# GBADVI.net
KiCad netlist of a schematic drawn in EAGLE
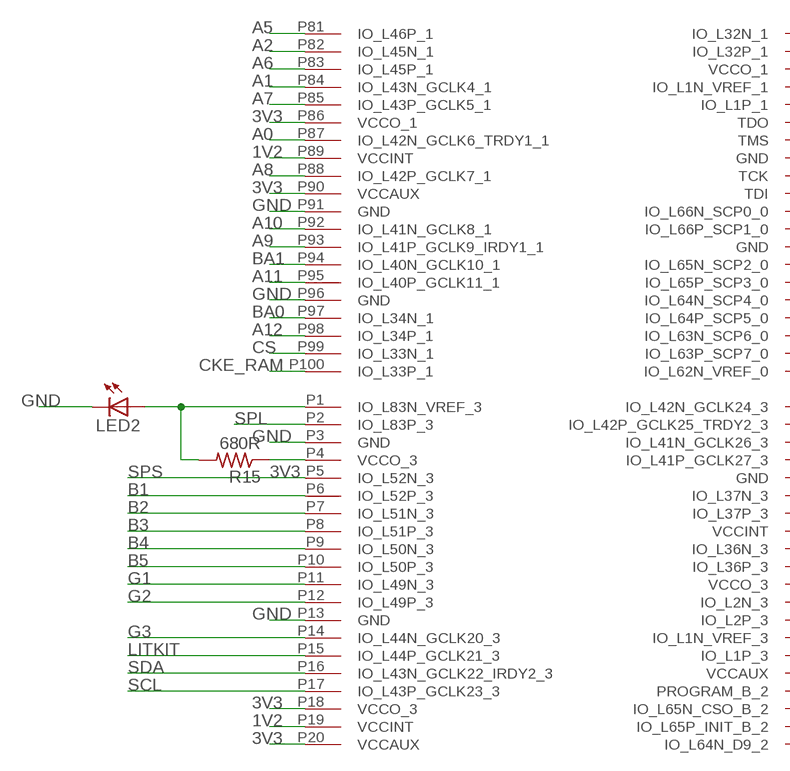
[diagram p0: schematic, sheet 1, part 1 of 2]
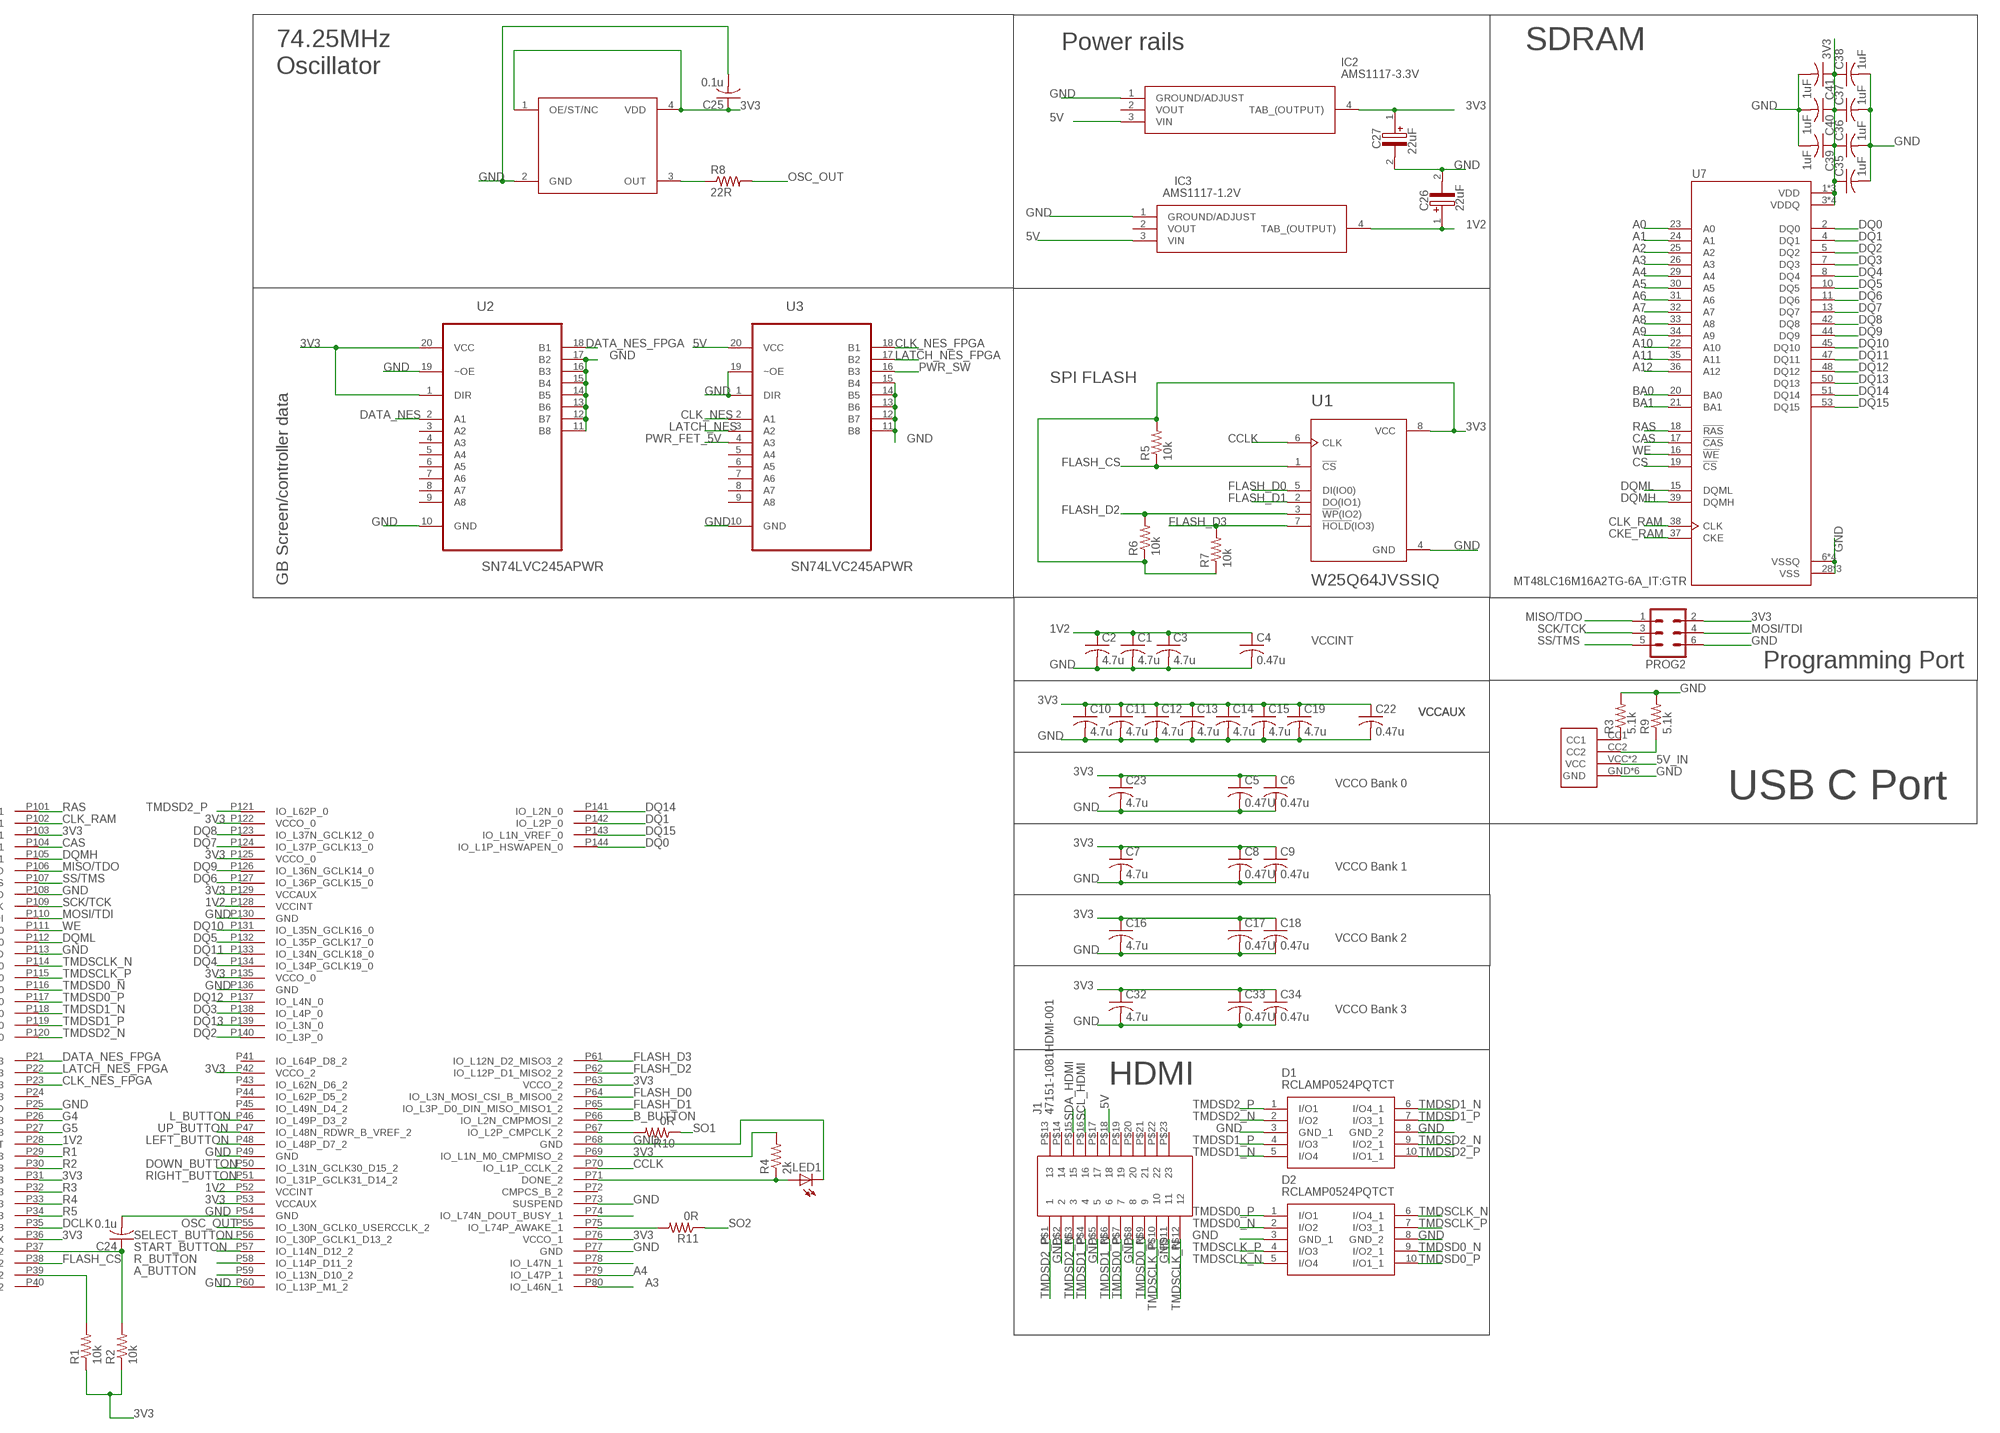
[diagram p1: schematic, sheet 1, part 2 of 2]
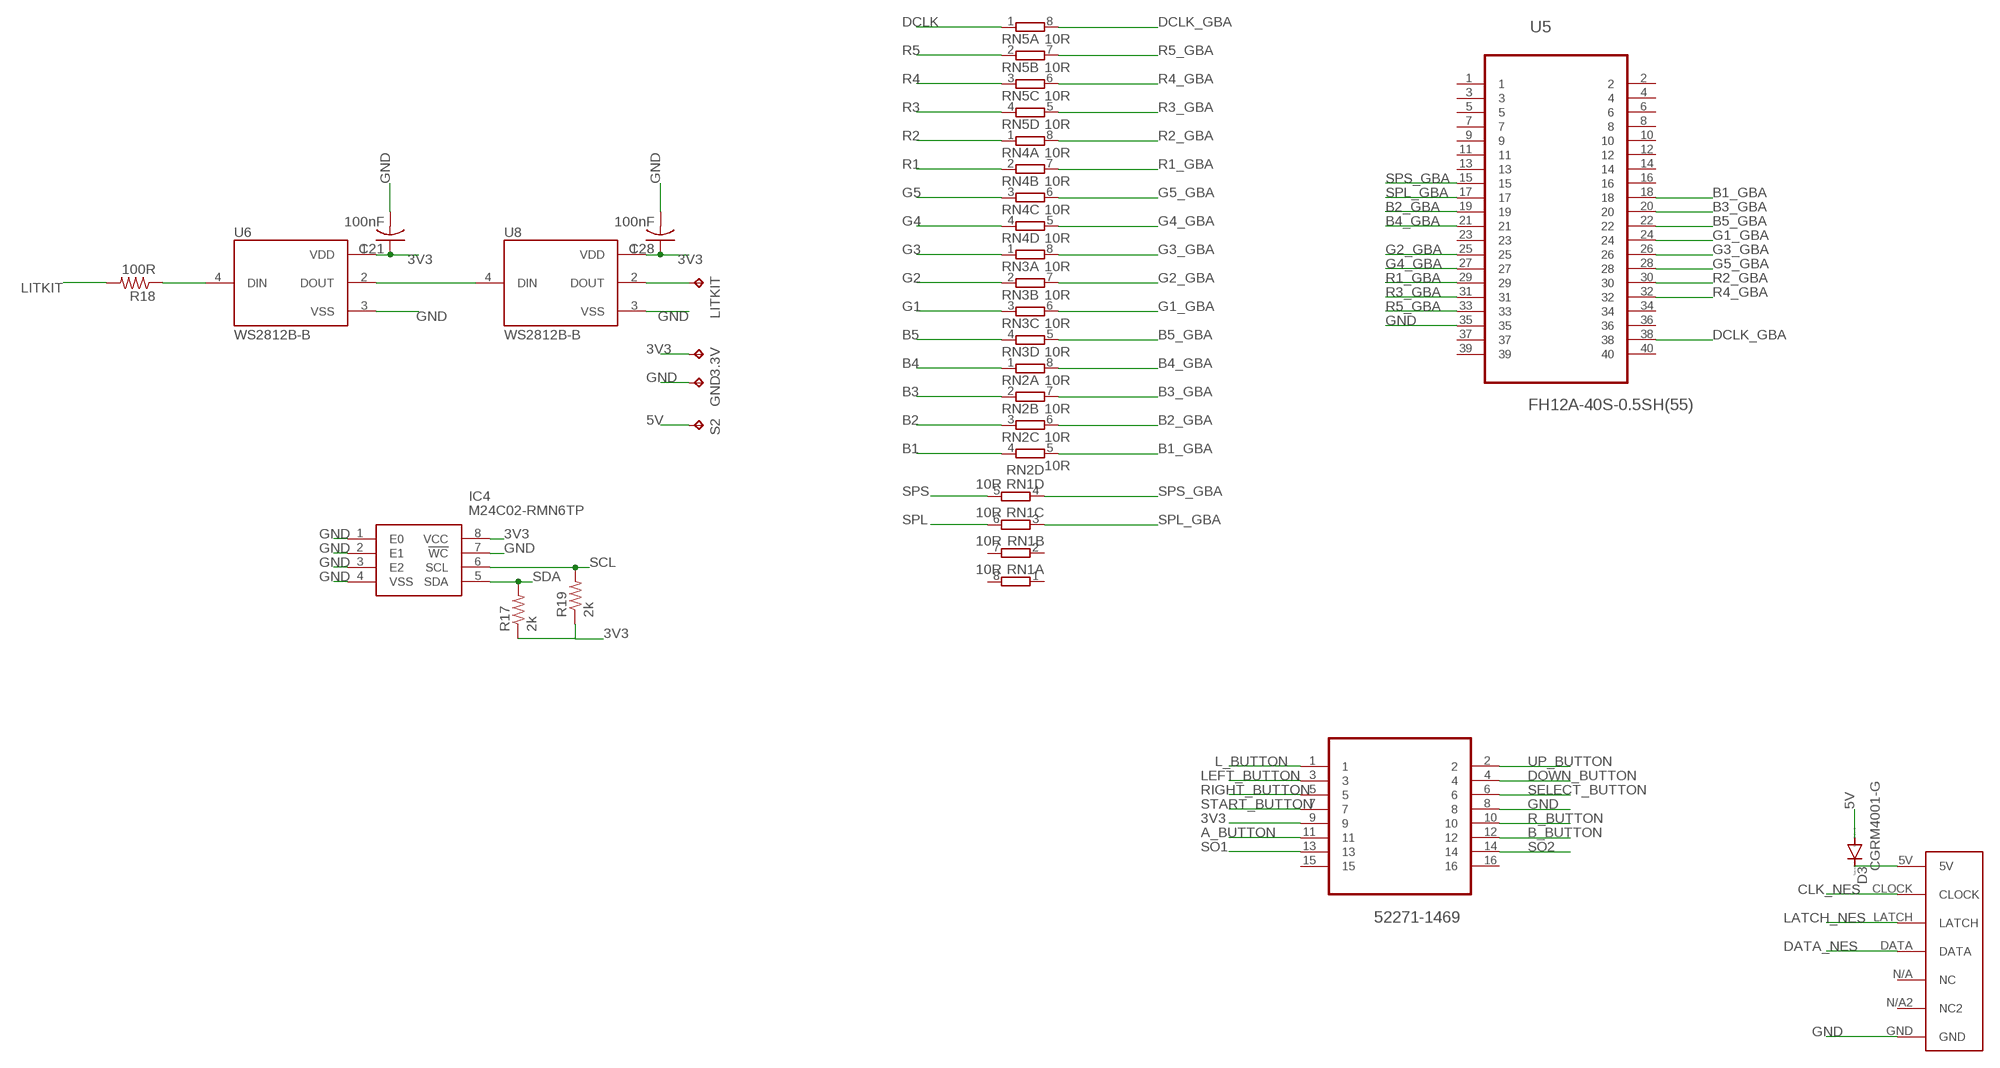
[diagram p2: schematic, sheet 2]
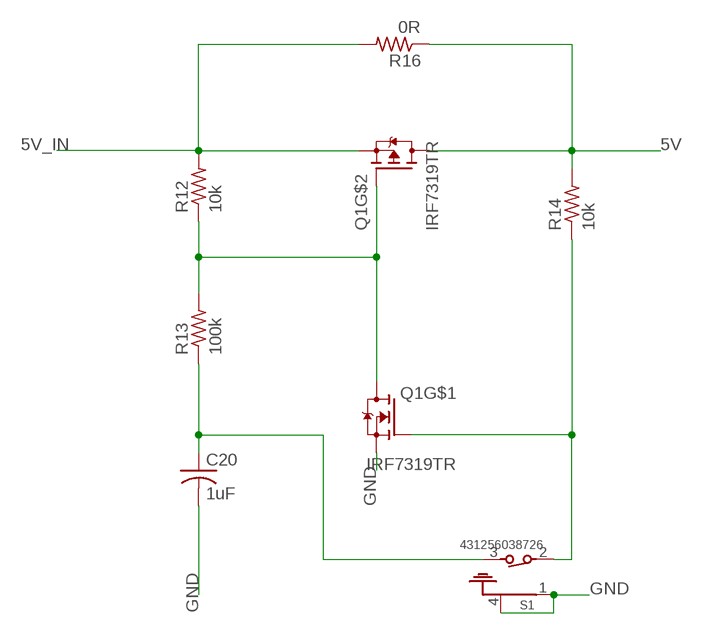
[diagram p3: schematic, sheet 3]

(export (version "E")
  (design (tool "Eeschema 10.0.6"))
  (components
    (comp (ref "3.3V")
      (value "TPB1,27")
      (footprint "eagle-import:B1,27")
      (libsource (lib "eagle-import") (part "TPB1,27"))
    )
    (comp (ref "C21")
      (value "100nF")
      (footprint "eagle-import:C0603")
      (libsource (lib "eagle-import") (part "C-USC0603"))
    )
    (comp (ref "C28")
      (value "100nF")
      (footprint "eagle-import:C0603")
      (libsource (lib "eagle-import") (part "C-USC0603"))
    )
    (comp (ref "D3")
      (value "CGRM4001-G")
      (footprint "eagle-import:SOD-123_MINI-SMA")
      (libsource (lib "eagle-import") (part "CGRM400-G1"))
    )
    (comp (ref "GND")
      (value "TPB1,27")
      (footprint "eagle-import:B1,27")
      (libsource (lib "eagle-import") (part "TPB1,27"))
    )
    (comp (ref "IC4")
      (value "M24C02-RMN6TP")
      (footprint "eagle-import:SOIC127P600X175-8N")
      (fields (field (name "MOUSER_PART_NUMBER") "511-M24C02-RMN6TP"))
      (libsource (lib "eagle-import") (part "M24C02-RMN6TP"))
    )
    (comp (ref "LITKIT")
      (value "TPB1,27")
      (footprint "eagle-import:B1,27")
      (libsource (lib "eagle-import") (part "TPB1,27"))
    )
    (comp (ref "R17")
      (value "2k")
      (footprint "eagle-import:R0603")
      (libsource (lib "eagle-import") (part "R-US_R0603"))
    )
    (comp (ref "R18")
      (value "100R")
      (footprint "eagle-import:R0603")
      (libsource (lib "eagle-import") (part "R-US_R0603"))
    )
    (comp (ref "R19")
      (value "2k")
      (footprint "eagle-import:R0603")
      (libsource (lib "eagle-import") (part "R-US_R0603"))
    )
    (comp (ref "RN1")
      (value "10R")
      (footprint "eagle-import:0603-ARV")
      (libsource (lib "eagle-import") (part "4R-N0603-ARV"))
    )
    (comp (ref "RN2")
      (value "10R")
      (footprint "eagle-import:0603-ARV")
      (libsource (lib "eagle-import") (part "4R-N0603-ARV"))
    )
    (comp (ref "RN3")
      (value "10R")
      (footprint "eagle-import:0603-ARV")
      (libsource (lib "eagle-import") (part "4R-N0603-ARV"))
    )
    (comp (ref "RN4")
      (value "10R")
      (footprint "eagle-import:0603-ARV")
      (libsource (lib "eagle-import") (part "4R-N0603-ARV"))
    )
    (comp (ref "RN5")
      (value "10R")
      (footprint "eagle-import:0603-ARV")
      (libsource (lib "eagle-import") (part "4R-N0603-ARV"))
    )
    (comp (ref "S2")
      (value "TPB1,27")
      (footprint "eagle-import:B1,27")
      (libsource (lib "eagle-import") (part "TPB1,27"))
    )
    (comp (ref "U$3")
      (value "SNES_CONT")
      (footprint "eagle-import:SNES_CONT")
      (libsource (lib "eagle-import") (part "SNES_CONT"))
    )
    (comp (ref "U4")
      (value "52271-1469")
      (footprint "eagle-import:MOLEX_52271-1469")
      (fields (field (name "MF") "Molex"))
      (libsource (lib "eagle-import") (part "52271-1469"))
    )
    (comp (ref "U5")
      (value "FH12A-40S-0.5SH(55)")
      (footprint "eagle-import:HIROSE_FH12A-40S-0.5SH(55)")
      (fields (field (name "MF") "Hirose Connector"))
      (libsource (lib "eagle-import") (part "FH12A-40S-0.5SH(55)"))
    )
    (comp (ref "U6")
      (value "WS2812B-B")
      (footprint "eagle-import:LED_WS2812B-B")
      (fields (field (name "MF") "Worldsemi"))
      (libsource (lib "eagle-import") (part "WS2812B-B"))
    )
    (comp (ref "U8")
      (value "WS2812B-B")
      (footprint "eagle-import:LED_WS2812B-B")
      (fields (field (name "MF") "Worldsemi"))
      (libsource (lib "eagle-import") (part "WS2812B-B"))
    )
    (comp (ref "C20")
      (value "1uF")
      (footprint "eagle-import:C0603")
      (libsource (lib "eagle-import") (part "C-USC0603"))
    )
    (comp (ref "Q1")
      (value "IRF7319TR")
      (footprint "eagle-import:SOIC127P600X175-8N")
      (fields (field (name "MF") "Infineon Technologies"))
      (libsource (lib "eagle-import") (part "IRF7319TR"))
    )
    (comp (ref "R12")
      (value "10k")
      (footprint "eagle-import:R0603")
      (libsource (lib "eagle-import") (part "R-US_R0603"))
    )
    (comp (ref "R13")
      (value "100k")
      (footprint "eagle-import:R0603")
      (libsource (lib "eagle-import") (part "R-US_R0603"))
    )
    (comp (ref "R14")
      (value "10k")
      (footprint "eagle-import:R0603")
      (libsource (lib "eagle-import") (part "R-US_R0603"))
    )
    (comp (ref "R16")
      (value "0R")
      (footprint "eagle-import:R0603")
      (libsource (lib "eagle-import") (part "R-US_R0603"))
    )
    (comp (ref "S1")
      (value "431256038726")
      (footprint "eagle-import:4312560387X6")
      (fields (field (name "MF") "Wurth Electronics"))
      (libsource (lib "eagle-import") (part "431256038726"))
    )
    (comp (ref "C1")
      (value "4.7u")
      (footprint "eagle-import:C0603")
      (libsource (lib "eagle-import") (part "rcl_334_C-USC0603"))
    )
    (comp (ref "C2")
      (value "4.7u")
      (footprint "eagle-import:C0603")
      (libsource (lib "eagle-import") (part "rcl_334_C-USC0603"))
    )
    (comp (ref "C3")
      (value "4.7u")
      (footprint "eagle-import:C0603")
      (libsource (lib "eagle-import") (part "rcl_334_C-USC0603"))
    )
    (comp (ref "C4")
      (value "0.47u")
      (footprint "eagle-import:C0603")
      (libsource (lib "eagle-import") (part "rcl_334_C-USC0603"))
    )
    (comp (ref "C5")
      (value "0.47U")
      (footprint "eagle-import:C0603")
      (libsource (lib "eagle-import") (part "rcl_334_C-USC0603"))
    )
    (comp (ref "C6")
      (value "0.47u")
      (footprint "eagle-import:C0603")
      (libsource (lib "eagle-import") (part "rcl_334_C-USC0603"))
    )
    (comp (ref "C7")
      (value "4.7u")
      (footprint "eagle-import:C0603")
      (libsource (lib "eagle-import") (part "rcl_334_C-USC0603"))
    )
    (comp (ref "C8")
      (value "0.47U")
      (footprint "eagle-import:C0603")
      (libsource (lib "eagle-import") (part "rcl_334_C-USC0603"))
    )
    (comp (ref "C9")
      (value "0.47u")
      (footprint "eagle-import:C0603")
      (libsource (lib "eagle-import") (part "rcl_334_C-USC0603"))
    )
    (comp (ref "C10")
      (value "4.7u")
      (footprint "eagle-import:C0603")
      (libsource (lib "eagle-import") (part "rcl_334_C-USC0603"))
    )
    (comp (ref "C11")
      (value "4.7u")
      (footprint "eagle-import:C0603")
      (libsource (lib "eagle-import") (part "rcl_334_C-USC0603"))
    )
    (comp (ref "C12")
      (value "4.7u")
      (footprint "eagle-import:C0603")
      (libsource (lib "eagle-import") (part "rcl_334_C-USC0603"))
    )
    (comp (ref "C13")
      (value "4.7u")
      (footprint "eagle-import:C0603")
      (libsource (lib "eagle-import") (part "rcl_334_C-USC0603"))
    )
    (comp (ref "C14")
      (value "4.7u")
      (footprint "eagle-import:C0603")
      (libsource (lib "eagle-import") (part "rcl_334_C-USC0603"))
    )
    (comp (ref "C15")
      (value "4.7u")
      (footprint "eagle-import:C0603")
      (libsource (lib "eagle-import") (part "rcl_334_C-USC0603"))
    )
    (comp (ref "C16")
      (value "4.7u")
      (footprint "eagle-import:C0603")
      (libsource (lib "eagle-import") (part "rcl_334_C-USC0603"))
    )
    (comp (ref "C17")
      (value "0.47U")
      (footprint "eagle-import:C0603")
      (libsource (lib "eagle-import") (part "rcl_334_C-USC0603"))
    )
    (comp (ref "C18")
      (value "0.47u")
      (footprint "eagle-import:C0603")
      (libsource (lib "eagle-import") (part "rcl_334_C-USC0603"))
    )
    (comp (ref "C19")
      (value "4.7u")
      (footprint "eagle-import:C0603")
      (libsource (lib "eagle-import") (part "rcl_334_C-USC0603"))
    )
    (comp (ref "C22")
      (value "0.47u")
      (footprint "eagle-import:C0603")
      (libsource (lib "eagle-import") (part "rcl_334_C-USC0603"))
    )
    (comp (ref "C23")
      (value "4.7u")
      (footprint "eagle-import:C0603")
      (libsource (lib "eagle-import") (part "rcl_334_C-USC0603"))
    )
    (comp (ref "C24")
      (value "0.1u")
      (footprint "eagle-import:C0603")
      (libsource (lib "eagle-import") (part "rcl_334_C-USC0603"))
    )
    (comp (ref "C25")
      (value "0.1u")
      (footprint "eagle-import:C0603")
      (libsource (lib "eagle-import") (part "rcl_334_C-USC0603"))
    )
    (comp (ref "C26")
      (value "22uF")
      (footprint "eagle-import:CAPPM3216X180N")
      (fields
        (field (name "MANUFACTURER_PART_NUMBER") "293D106X9016A2TE3")
        (field (name "MOUSER2_PART_NUMBER") "74-293D106X9016A2TE3")
      )
      (libsource (lib "eagle-import") (part "293D106X9016A2TE3"))
    )
    (comp (ref "C27")
      (value "22uF")
      (footprint "eagle-import:CAPPM3216X180N")
      (fields
        (field (name "MANUFACTURER_PART_NUMBER") "293D106X9016A2TE3")
        (field (name "MOUSER2_PART_NUMBER") "74-293D106X9016A2TE3")
      )
      (libsource (lib "eagle-import") (part "293D106X9016A2TE3"))
    )
    (comp (ref "C32")
      (value "4.7u")
      (footprint "eagle-import:C0603")
      (libsource (lib "eagle-import") (part "rcl_334_C-USC0603"))
    )
    (comp (ref "C33")
      (value "0.47U")
      (footprint "eagle-import:C0603")
      (libsource (lib "eagle-import") (part "rcl_334_C-USC0603"))
    )
    (comp (ref "C34")
      (value "0.47u")
      (footprint "eagle-import:C0603")
      (libsource (lib "eagle-import") (part "rcl_334_C-USC0603"))
    )
    (comp (ref "C35")
      (value "1uF")
      (footprint "eagle-import:C0603")
      (libsource (lib "eagle-import") (part "rcl_334_C-USC0603"))
    )
    (comp (ref "C36")
      (value "1uF")
      (footprint "eagle-import:C0603")
      (libsource (lib "eagle-import") (part "rcl_334_C-USC0603"))
    )
    (comp (ref "C37")
      (value "1uF")
      (footprint "eagle-import:C0603")
      (libsource (lib "eagle-import") (part "rcl_334_C-USC0603"))
    )
    (comp (ref "C38")
      (value "1uF")
      (footprint "eagle-import:C0603")
      (libsource (lib "eagle-import") (part "rcl_334_C-USC0603"))
    )
    (comp (ref "C39")
      (value "1uF")
      (footprint "eagle-import:C0603")
      (libsource (lib "eagle-import") (part "rcl_334_C-USC0603"))
    )
    (comp (ref "C40")
      (value "1uF")
      (footprint "eagle-import:C0603")
      (libsource (lib "eagle-import") (part "rcl_334_C-USC0603"))
    )
    (comp (ref "C41")
      (value "1uF")
      (footprint "eagle-import:C0603")
      (libsource (lib "eagle-import") (part "rcl_334_C-USC0603"))
    )
    (comp (ref "D1")
      (value "RCLAMP0524PQTCT")
      (footprint "eagle-import:RCLAMP0524P")
      (fields (field (name "MOUSER2_PART_NUMBER") "947-RCLAMP0524PQTCT"))
      (libsource (lib "eagle-import") (part "RCLAMP0524PQTCT"))
    )
    (comp (ref "D2")
      (value "RCLAMP0524PQTCT")
      (footprint "eagle-import:RCLAMP0524P")
      (fields (field (name "MOUSER2_PART_NUMBER") "947-RCLAMP0524PQTCT"))
      (libsource (lib "eagle-import") (part "RCLAMP0524PQTCT"))
    )
    (comp (ref "IC2")
      (value "AMS1117-3.3V")
      (footprint "eagle-import:SOT229P700X180-4N")
      (fields (field (name "MANUFACTURER_PART_NUMBER") "ams1117-3.3v"))
      (libsource (lib "eagle-import") (part "AMS1117-3.3V"))
    )
    (comp (ref "IC3")
      (value "AMS1117-1.2V")
      (footprint "eagle-import:SOT229P700X180-4N")
      (fields (field (name "MANUFACTURER_PART_NUMBER") "ams1117-3.3v"))
      (libsource (lib "eagle-import") (part "AMS1117-3.3V"))
    )
    (comp (ref "J1")
      (value "47151-1081HDMI-001")
      (footprint "eagle-import:HDMI-001")
      (libsource (lib "eagle-import") (part "47151-1081HDMI-001"))
    )
    (comp (ref "LED1")
      (value "LEDCHIP-LED0603")
      (footprint "eagle-import:CHIP-LED0603")
      (libsource (lib "eagle-import") (part "LEDCHIP-LED0603"))
    )
    (comp (ref "LED2")
      (value "LEDCHIP-LED0603")
      (footprint "eagle-import:CHIP-LED0603")
      (libsource (lib "eagle-import") (part "LEDCHIP-LED0603"))
    )
    (comp (ref "PROG2")
      (value "MA03-2")
      (footprint "eagle-import:MA03-2")
      (libsource (lib "eagle-import") (part "MA03-2"))
    )
    (comp (ref "R1")
      (value "10k")
      (footprint "eagle-import:R0603")
      (libsource (lib "eagle-import") (part "R-US_R0603"))
    )
    (comp (ref "R2")
      (value "10k")
      (footprint "eagle-import:R0603")
      (libsource (lib "eagle-import") (part "R-US_R0603"))
    )
    (comp (ref "R3")
      (value "5.1k")
      (footprint "eagle-import:R0603")
      (libsource (lib "eagle-import") (part "R-US_R0603"))
    )
    (comp (ref "R4")
      (value "2k")
      (footprint "eagle-import:R0603")
      (libsource (lib "eagle-import") (part "R-US_R0603"))
    )
    (comp (ref "R5")
      (value "10k")
      (footprint "eagle-import:R0603")
      (libsource (lib "eagle-import") (part "R-US_R0603"))
    )
    (comp (ref "R6")
      (value "10k")
      (footprint "eagle-import:R0603")
      (libsource (lib "eagle-import") (part "R-US_R0603"))
    )
    (comp (ref "R7")
      (value "10k")
      (footprint "eagle-import:R0603")
      (libsource (lib "eagle-import") (part "R-US_R0603"))
    )
    (comp (ref "R8")
      (value "22R")
      (footprint "eagle-import:R0603")
      (libsource (lib "eagle-import") (part "resistor_348_R-US_R0603"))
    )
    (comp (ref "R9")
      (value "5.1k")
      (footprint "eagle-import:R0603")
      (libsource (lib "eagle-import") (part "R-US_R0603"))
    )
    (comp (ref "R10")
      (value "0R")
      (footprint "eagle-import:R0603")
      (libsource (lib "eagle-import") (part "R-US_R0603"))
    )
    (comp (ref "R11")
      (value "0R")
      (footprint "eagle-import:R0603")
      (libsource (lib "eagle-import") (part "R-US_R0603"))
    )
    (comp (ref "R15")
      (value "680R")
      (footprint "eagle-import:R0603")
      (libsource (lib "eagle-import") (part "R-US_R0603"))
    )
    (comp (ref "U$1")
      (value "O50327425MEDH4MI")
      (footprint "eagle-import:OSC_ECS-3518-640-B-TR")
      (libsource (lib "eagle-import") (part "SIT1602BI-82-33E-75.250000YO50327425MEDH4MI"))
    )
    (comp (ref "U$2")
      (value "XC6SLX9-2TQG144C")
      (footprint "eagle-import:TQ144")
      (fields (field (name "MF") "Xilinx Inc."))
      (libsource (lib "eagle-import") (part "XC6SLX9-2TQG144C"))
    )
    (comp (ref "U$5")
      (value "POWER_USBC")
      (footprint "eagle-import:USB-C")
      (libsource (lib "eagle-import") (part "POWER_USBC"))
    )
    (comp (ref "U1")
      (value "W25Q64JVSSIQ")
      (footprint "eagle-import:SOIC127P790X216-8N")
      (fields (field (name "MF") "Winbond Electronics") (field (name "MP") "W25Q64BVSSIG"))
      (libsource (lib "eagle-import") (part "W25Q64BVSSIG"))
    )
    (comp (ref "U2")
      (value "SN74LVC245APWR")
      (footprint "eagle-import:SOP65P640X120-20N")
      (fields (field (name "DIGI-KEY_PART_NUMBER") "296-1233-1-ND") (field (name "MF") "Texas Instruments"))
      (libsource (lib "eagle-import") (part "SN74LVC245APWR"))
    )
    (comp (ref "U3")
      (value "SN74LVC245APWR")
      (footprint "eagle-import:SOP65P640X120-20N")
      (fields (field (name "DIGI-KEY_PART_NUMBER") "296-1233-1-ND") (field (name "MF") "Texas Instruments"))
      (libsource (lib "eagle-import") (part "SN74LVC245APWR"))
    )
    (comp (ref "U7")
      (value "MT48LC16M16A2TG-6A_IT:GTR")
      (footprint "eagle-import:SOP80P1176X120-54N")
      (fields (field (name "MF") "Alliance Memory,") (field (name "MP") "MT48LC16M16A2TG-6A IT:GTR"))
      (libsource (lib "eagle-import") (part "MT48LC16M16A2TG-6A_IT{colon}GTR"))
    )
  )
  (nets
    (net (code "1") (name "1V2") (class "Default")
      (node (ref "C1") (pin "1") (pinfunction "1_1") (pintype "passive"))
      (node (ref "C2") (pin "1") (pinfunction "1_1") (pintype "passive"))
      (node (ref "C26") (pin "1") (pinfunction "+_1") (pintype "bidirectional"))
      (node (ref "C3") (pin "1") (pinfunction "1_1") (pintype "passive"))
      (node (ref "C4") (pin "1") (pinfunction "1_1") (pintype "passive"))
      (node (ref "IC3") (pin "4") (pinfunction "TAB_(OUTPUT)_4") (pintype "bidirectional"))
      (node (ref "U$2") (pin "P128") (pinfunction "VCCINT_P128") (pintype "bidirectional"))
      (node (ref "U$2") (pin "P19") (pinfunction "VCCINT_P19") (pintype "bidirectional"))
      (node (ref "U$2") (pin "P28") (pinfunction "VCCINT_P28") (pintype "bidirectional"))
      (node (ref "U$2") (pin "P52") (pinfunction "VCCINT_P52") (pintype "bidirectional"))
      (node (ref "U$2") (pin "P89") (pinfunction "VCCINT_P89") (pintype "bidirectional"))
    )
    (net (code "2") (name "3V3") (class "Default")
      (node (ref "3.3V") (pin "TP") (pinfunction "TP_TP") (pintype "input"))
      (node (ref "C10") (pin "1") (pinfunction "1_1") (pintype "passive"))
      (node (ref "C11") (pin "1") (pinfunction "1_1") (pintype "passive"))
      (node (ref "C12") (pin "1") (pinfunction "1_1") (pintype "passive"))
      (node (ref "C13") (pin "1") (pinfunction "1_1") (pintype "passive"))
      (node (ref "C14") (pin "1") (pinfunction "1_1") (pintype "passive"))
      (node (ref "C15") (pin "1") (pinfunction "1_1") (pintype "passive"))
      (node (ref "C16") (pin "1") (pinfunction "1_1") (pintype "passive"))
      (node (ref "C17") (pin "1") (pinfunction "1_1") (pintype "passive"))
      (node (ref "C18") (pin "1") (pinfunction "1_1") (pintype "passive"))
      (node (ref "C19") (pin "1") (pinfunction "1_1") (pintype "passive"))
      (node (ref "C21") (pin "1") (pinfunction "1_1") (pintype "passive"))
      (node (ref "C22") (pin "1") (pinfunction "1_1") (pintype "passive"))
      (node (ref "C23") (pin "1") (pinfunction "1_1") (pintype "passive"))
      (node (ref "C25") (pin "1") (pinfunction "1_1") (pintype "passive"))
      (node (ref "C27") (pin "1") (pinfunction "+_1") (pintype "bidirectional"))
      (node (ref "C28") (pin "1") (pinfunction "1_1") (pintype "passive"))
      (node (ref "C32") (pin "1") (pinfunction "1_1") (pintype "passive"))
      (node (ref "C33") (pin "1") (pinfunction "1_1") (pintype "passive"))
      (node (ref "C34") (pin "1") (pinfunction "1_1") (pintype "passive"))
      (node (ref "C35") (pin "1") (pinfunction "1_1") (pintype "passive"))
      (node (ref "C36") (pin "1") (pinfunction "1_1") (pintype "passive"))
      (node (ref "C37") (pin "1") (pinfunction "1_1") (pintype "passive"))
      (node (ref "C38") (pin "1") (pinfunction "1_1") (pintype "passive"))
      (node (ref "C39") (pin "1") (pinfunction "1_1") (pintype "passive"))
      (node (ref "C40") (pin "1") (pinfunction "1_1") (pintype "passive"))
      (node (ref "C41") (pin "1") (pinfunction "1_1") (pintype "passive"))
      (node (ref "C5") (pin "1") (pinfunction "1_1") (pintype "passive"))
      (node (ref "C6") (pin "1") (pinfunction "1_1") (pintype "passive"))
      (node (ref "C7") (pin "1") (pinfunction "1_1") (pintype "passive"))
      (node (ref "C8") (pin "1") (pinfunction "1_1") (pintype "passive"))
      (node (ref "C9") (pin "1") (pinfunction "1_1") (pintype "passive"))
      (node (ref "IC2") (pin "4") (pinfunction "TAB_(OUTPUT)_4") (pintype "bidirectional"))
      (node (ref "IC4") (pin "8") (pinfunction "VCC_8") (pintype "bidirectional"))
      (node (ref "PROG2") (pin "2") (pinfunction "2_2") (pintype "passive"))
      (node (ref "R1") (pin "1") (pinfunction "1_1") (pintype "passive"))
      (node (ref "R15") (pin "1") (pinfunction "1_1") (pintype "passive"))
      (node (ref "R17") (pin "1") (pinfunction "1_1") (pintype "passive"))
      (node (ref "R19") (pin "1") (pinfunction "1_1") (pintype "passive"))
      (node (ref "R2") (pin "1") (pinfunction "1_1") (pintype "passive"))
      (node (ref "R4") (pin "2") (pinfunction "2_2") (pintype "passive"))
      (node (ref "R5") (pin "2") (pinfunction "2_2") (pintype "passive"))
      (node (ref "R6") (pin "1") (pinfunction "1_1") (pintype "passive"))
      (node (ref "R7") (pin "1") (pinfunction "1_1") (pintype "passive"))
      (node (ref "U$1") (pin "1") (pinfunction "OE/ST/NC_1") (pintype "bidirectional"))
      (node (ref "U$1") (pin "4") (pinfunction "VDD_4") (pintype "bidirectional"))
      (node (ref "U$2") (pin "P103") (pinfunction "VCCO_1_P103") (pintype "bidirectional"))
      (node (ref "U$2") (pin "P122") (pinfunction "VCCO_0_P122") (pintype "bidirectional"))
      (node (ref "U$2") (pin "P125") (pinfunction "VCCO_0_P125") (pintype "bidirectional"))
      (node (ref "U$2") (pin "P129") (pinfunction "VCCAUX_P129") (pintype "bidirectional"))
      (node (ref "U$2") (pin "P135") (pinfunction "VCCO_0_P135") (pintype "bidirectional"))
      (node (ref "U$2") (pin "P18") (pinfunction "VCCO_3_P18") (pintype "bidirectional"))
      (node (ref "U$2") (pin "P20") (pinfunction "VCCAUX_P20") (pintype "bidirectional"))
      (node (ref "U$2") (pin "P31") (pinfunction "VCCO_3_P31") (pintype "bidirectional"))
      (node (ref "U$2") (pin "P36") (pinfunction "VCCAUX_P36") (pintype "bidirectional"))
      (node (ref "U$2") (pin "P4") (pinfunction "VCCO_3_P4") (pintype "bidirectional"))
      (node (ref "U$2") (pin "P42") (pinfunction "VCCO_2_P42") (pintype "bidirectional"))
      (node (ref "U$2") (pin "P53") (pinfunction "VCCAUX_P53") (pintype "bidirectional"))
      (node (ref "U$2") (pin "P63") (pinfunction "VCCO_2_P63") (pintype "bidirectional"))
      (node (ref "U$2") (pin "P69") (pinfunction "IO_L1N_M0_CMPMISO_2_P69") (pintype "bidirectional"))
      (node (ref "U$2") (pin "P76") (pinfunction "VCCO_1_P76") (pintype "bidirectional"))
      (node (ref "U$2") (pin "P86") (pinfunction "VCCO_1_P86") (pintype "bidirectional"))
      (node (ref "U$2") (pin "P90") (pinfunction "VCCAUX_P90") (pintype "bidirectional"))
      (node (ref "U1") (pin "8") (pinfunction "VCC_8") (pintype "power_in"))
      (node (ref "U2") (pin "1") (pinfunction "DIR_1") (pintype "input"))
      (node (ref "U2") (pin "20") (pinfunction "VCC_20") (pintype "power_in"))
      (node (ref "U4") (pin "9") (pinfunction "9_9") (pintype "passive"))
      (node (ref "U6") (pin "1") (pinfunction "VDD_1") (pintype "power_in"))
      (node (ref "U7") (pin "1") (pinfunction "VDD_1") (pintype "power_in"))
      (node (ref "U7") (pin "14") (pinfunction "VDD_14") (pintype "power_in"))
      (node (ref "U7") (pin "27") (pinfunction "VDD_27") (pintype "power_in"))
      (node (ref "U7") (pin "3") (pinfunction "VDDQ_3") (pintype "power_in"))
      (node (ref "U7") (pin "43") (pinfunction "VDDQ_43") (pintype "power_in"))
      (node (ref "U7") (pin "49") (pinfunction "VDDQ_49") (pintype "power_in"))
      (node (ref "U7") (pin "9") (pinfunction "VDDQ_9") (pintype "power_in"))
      (node (ref "U8") (pin "1") (pinfunction "VDD_1") (pintype "power_in"))
    )
    (net (code "3") (name "5V") (class "Default")
      (node (ref "D3") (pin "A") (pinfunction "A_A") (pintype "passive"))
      (node (ref "IC2") (pin "3") (pinfunction "VIN_3") (pintype "bidirectional"))
      (node (ref "IC3") (pin "3") (pinfunction "VIN_3") (pintype "bidirectional"))
      (node (ref "J1") (pin "P$18") (pinfunction "18_P$18") (pintype "bidirectional"))
      (node (ref "Q1") (pin "5") (pinfunction "D_5") (pintype "passive"))
      (node (ref "Q1") (pin "6") (pinfunction "D_6") (pintype "passive"))
      (node (ref "R14") (pin "2") (pinfunction "2_2") (pintype "passive"))
      (node (ref "R16") (pin "1") (pinfunction "1_1") (pintype "passive"))
      (node (ref "S2") (pin "TP") (pinfunction "TP_TP") (pintype "input"))
      (node (ref "U3") (pin "20") (pinfunction "VCC_20") (pintype "power_in"))
    )
    (net (code "4") (name "5V_IN") (class "Default")
      (node (ref "Q1") (pin "3") (pinfunction "S_3") (pintype "passive"))
      (node (ref "R12") (pin "2") (pinfunction "2_2") (pintype "passive"))
      (node (ref "R16") (pin "2") (pinfunction "2_2") (pintype "passive"))
      (node (ref "U$5") (pin "VCC") (pinfunction "VCC_VCC") (pintype "bidirectional"))
      (node (ref "U$5") (pin "VCC1") (pinfunction "VCC_VCC1") (pintype "bidirectional"))
    )
    (net (code "5") (name "A0") (class "Default")
      (node (ref "U$2") (pin "P87") (pinfunction "IO_L42N_GCLK6_TRDY1_1_P87") (pintype "bidirectional"))
      (node (ref "U7") (pin "23") (pinfunction "A0_23") (pintype "input"))
    )
    (net (code "6") (name "A1") (class "Default")
      (node (ref "U$2") (pin "P84") (pinfunction "IO_L43N_GCLK4_1_P84") (pintype "bidirectional"))
      (node (ref "U7") (pin "24") (pinfunction "A1_24") (pintype "input"))
    )
    (net (code "7") (name "A2") (class "Default")
      (node (ref "U$2") (pin "P82") (pinfunction "IO_L45N_1_P82") (pintype "bidirectional"))
      (node (ref "U7") (pin "25") (pinfunction "A2_25") (pintype "input"))
    )
    (net (code "8") (name "A3") (class "Default")
      (node (ref "U$2") (pin "P80") (pinfunction "IO_L46N_1_P80") (pintype "bidirectional"))
      (node (ref "U7") (pin "26") (pinfunction "A3_26") (pintype "input"))
    )
    (net (code "9") (name "A4") (class "Default")
      (node (ref "U$2") (pin "P79") (pinfunction "IO_L47P_1_P79") (pintype "bidirectional"))
      (node (ref "U7") (pin "29") (pinfunction "A4_29") (pintype "input"))
    )
    (net (code "10") (name "A5") (class "Default")
      (node (ref "U$2") (pin "P81") (pinfunction "IO_L46P_1_P81") (pintype "bidirectional"))
      (node (ref "U7") (pin "30") (pinfunction "A5_30") (pintype "input"))
    )
    (net (code "11") (name "A6") (class "Default")
      (node (ref "U$2") (pin "P83") (pinfunction "IO_L45P_1_P83") (pintype "bidirectional"))
      (node (ref "U7") (pin "31") (pinfunction "A6_31") (pintype "input"))
    )
    (net (code "12") (name "A7") (class "Default")
      (node (ref "U$2") (pin "P85") (pinfunction "IO_L43P_GCLK5_1_P85") (pintype "bidirectional"))
      (node (ref "U7") (pin "32") (pinfunction "A7_32") (pintype "input"))
    )
    (net (code "13") (name "A8") (class "Default")
      (node (ref "U$2") (pin "P88") (pinfunction "IO_L42P_GCLK7_1_P88") (pintype "bidirectional"))
      (node (ref "U7") (pin "33") (pinfunction "A8_33") (pintype "input"))
    )
    (net (code "14") (name "A9") (class "Default")
      (node (ref "U$2") (pin "P93") (pinfunction "IO_L41P_GCLK9_IRDY1_1_P93") (pintype "bidirectional"))
      (node (ref "U7") (pin "34") (pinfunction "A9_34") (pintype "input"))
    )
    (net (code "15") (name "A10") (class "Default")
      (node (ref "U$2") (pin "P92") (pinfunction "IO_L41N_GCLK8_1_P92") (pintype "bidirectional"))
      (node (ref "U7") (pin "22") (pinfunction "A10_22") (pintype "input"))
    )
    (net (code "16") (name "A11") (class "Default")
      (node (ref "U$2") (pin "P95") (pinfunction "IO_L40P_GCLK11_1_P95") (pintype "bidirectional"))
      (node (ref "U7") (pin "35") (pinfunction "A11_35") (pintype "input"))
    )
    (net (code "17") (name "A12") (class "Default")
      (node (ref "U$2") (pin "P98") (pinfunction "IO_L34P_1_P98") (pintype "bidirectional"))
      (node (ref "U7") (pin "36") (pinfunction "A12_36") (pintype "input"))
    )
    (net (code "18") (name "A_BUTTON") (class "Default")
      (node (ref "U$2") (pin "P59") (pinfunction "IO_L13N_D10_2_P59") (pintype "bidirectional"))
      (node (ref "U4") (pin "11") (pinfunction "11_11") (pintype "passive"))
    )
    (net (code "19") (name "B1") (class "Default")
      (node (ref "RN2") (pin "4") (pinfunction "1_4") (pintype "passive"))
      (node (ref "U$2") (pin "P6") (pinfunction "IO_L52P_3_P6") (pintype "bidirectional"))
    )
    (net (code "20") (name "B1_GBA") (class "Default")
      (node (ref "RN2") (pin "5") (pinfunction "2_5") (pintype "passive"))
      (node (ref "U5") (pin "18") (pinfunction "18_18") (pintype "passive"))
    )
    (net (code "21") (name "B2") (class "Default")
      (node (ref "RN2") (pin "3") (pinfunction "1_3") (pintype "passive"))
      (node (ref "U$2") (pin "P7") (pinfunction "IO_L51N_3_P7") (pintype "bidirectional"))
    )
    (net (code "22") (name "B2_GBA") (class "Default")
      (node (ref "RN2") (pin "6") (pinfunction "2_6") (pintype "passive"))
      (node (ref "U5") (pin "19") (pinfunction "19_19") (pintype "passive"))
    )
    (net (code "23") (name "B3") (class "Default")
      (node (ref "RN2") (pin "2") (pinfunction "1_2") (pintype "passive"))
      (node (ref "U$2") (pin "P8") (pinfunction "IO_L51P_3_P8") (pintype "bidirectional"))
    )
    (net (code "24") (name "B3_GBA") (class "Default")
      (node (ref "RN2") (pin "7") (pinfunction "2_7") (pintype "passive"))
      (node (ref "U5") (pin "20") (pinfunction "20_20") (pintype "passive"))
    )
    (net (code "25") (name "B4") (class "Default")
      (node (ref "RN2") (pin "1") (pinfunction "1_1") (pintype "passive"))
      (node (ref "U$2") (pin "P9") (pinfunction "IO_L50N_3_P9") (pintype "bidirectional"))
    )
    (net (code "26") (name "B4_GBA") (class "Default")
      (node (ref "RN2") (pin "8") (pinfunction "2_8") (pintype "passive"))
      (node (ref "U5") (pin "21") (pinfunction "21_21") (pintype "passive"))
    )
    (net (code "27") (name "B5") (class "Default")
      (node (ref "RN3") (pin "4") (pinfunction "1_4") (pintype "passive"))
      (node (ref "U$2") (pin "P10") (pinfunction "IO_L50P_3_P10") (pintype "bidirectional"))
    )
    (net (code "28") (name "B5_GBA") (class "Default")
      (node (ref "RN3") (pin "5") (pinfunction "2_5") (pintype "passive"))
      (node (ref "U5") (pin "22") (pinfunction "22_22") (pintype "passive"))
    )
    (net (code "29") (name "BA0") (class "Default")
      (node (ref "U$2") (pin "P97") (pinfunction "IO_L34N_1_P97") (pintype "bidirectional"))
      (node (ref "U7") (pin "20") (pinfunction "BA0_20") (pintype "input"))
    )
    (net (code "30") (name "BA1") (class "Default")
      (node (ref "U$2") (pin "P94") (pinfunction "IO_L40N_GCLK10_1_P94") (pintype "bidirectional"))
      (node (ref "U7") (pin "21") (pinfunction "BA1_21") (pintype "input"))
    )
    (net (code "31") (name "B_BUTTON") (class "Default")
      (node (ref "U$2") (pin "P66") (pinfunction "IO_L2N_CMPMOSI_2_P66") (pintype "bidirectional"))
      (node (ref "U4") (pin "12") (pinfunction "12_12") (pintype "passive"))
    )
    (net (code "32") (name "CAS") (class "Default")
      (node (ref "U$2") (pin "P104") (pinfunction "IO_L1N_VREF_1_P104") (pintype "bidirectional"))
      (node (ref "U7") (pin "17") (pinfunction "~{CAS}_17") (pintype "input"))
    )
    (net (code "33") (name "CCLK") (class "Default")
      (node (ref "U$2") (pin "P70") (pinfunction "IO_L1P_CCLK_2_P70") (pintype "bidirectional"))
      (node (ref "U1") (pin "6") (pinfunction "CLK_6") (pintype "input"))
    )
    (net (code "34") (name "CKE_RAM") (class "Default")
      (node (ref "U$2") (pin "P100") (pinfunction "IO_L33P_1_P100") (pintype "bidirectional"))
      (node (ref "U7") (pin "37") (pinfunction "CKE_37") (pintype "input"))
    )
    (net (code "35") (name "CLK_NES") (class "Default")
      (node (ref "U$3") (pin "CLOCK") (pinfunction "CLOCK_CLOCK") (pintype "bidirectional"))
      (node (ref "U3") (pin "2") (pinfunction "A1_2") (pintype "bidirectional"))
    )
    (net (code "36") (name "CLK_NES_FPGA") (class "Default")
      (node (ref "U$2") (pin "P23") (pinfunction "IO_L41N_GCLK26_3_P23") (pintype "bidirectional"))
      (node (ref "U3") (pin "18") (pinfunction "B1_18") (pintype "bidirectional"))
    )
    (net (code "37") (name "CLK_RAM") (class "Default")
      (node (ref "U$2") (pin "P102") (pinfunction "IO_L32P_1_P102") (pintype "bidirectional"))
      (node (ref "U7") (pin "38") (pinfunction "CLK_38") (pintype "input"))
    )
    (net (code "38") (name "CS") (class "Default")
      (node (ref "U$2") (pin "P99") (pinfunction "IO_L33N_1_P99") (pintype "bidirectional"))
      (node (ref "U7") (pin "19") (pinfunction "~{CS}_19") (pintype "input"))
    )
    (net (code "39") (name "DATA_NES") (class "Default")
      (node (ref "U$3") (pin "DATA") (pinfunction "DATA_DATA") (pintype "bidirectional"))
      (node (ref "U2") (pin "2") (pinfunction "A1_2") (pintype "bidirectional"))
    )
    (net (code "40") (name "DATA_NES_FPGA") (class "Default")
      (node (ref "U$2") (pin "P21") (pinfunction "IO_L42N_GCLK24_3_P21") (pintype "bidirectional"))
      (node (ref "U2") (pin "18") (pinfunction "B1_18") (pintype "bidirectional"))
    )
    (net (code "41") (name "DCLK") (class "Default")
      (node (ref "RN5") (pin "1") (pinfunction "1_1") (pintype "passive"))
      (node (ref "U$2") (pin "P35") (pinfunction "IO_L1P_3_P35") (pintype "bidirectional"))
    )
    (net (code "42") (name "DCLK_GBA") (class "Default")
      (node (ref "RN5") (pin "8") (pinfunction "2_8") (pintype "passive"))
      (node (ref "U5") (pin "38") (pinfunction "38_38") (pintype "passive"))
    )
    (net (code "43") (name "DOWN_BUTTON") (class "Default")
      (node (ref "U$2") (pin "P50") (pinfunction "IO_L31N_GCLK30_D15_2_P50") (pintype "bidirectional"))
      (node (ref "U4") (pin "4") (pinfunction "4_4") (pintype "passive"))
    )
    (net (code "44") (name "DQ0") (class "Default")
      (node (ref "U$2") (pin "P144") (pinfunction "IO_L1P_HSWAPEN_0_P144") (pintype "bidirectional"))
      (node (ref "U7") (pin "2") (pinfunction "DQ0_2") (pintype "bidirectional"))
    )
    (net (code "45") (name "DQ1") (class "Default")
      (node (ref "U$2") (pin "P142") (pinfunction "IO_L2P_0_P142") (pintype "bidirectional"))
      (node (ref "U7") (pin "4") (pinfunction "DQ1_4") (pintype "bidirectional"))
    )
    (net (code "46") (name "DQ2") (class "Default")
      (node (ref "U$2") (pin "P140") (pinfunction "IO_L3P_0_P140") (pintype "bidirectional"))
      (node (ref "U7") (pin "5") (pinfunction "DQ2_5") (pintype "bidirectional"))
    )
    (net (code "47") (name "DQ3") (class "Default")
      (node (ref "U$2") (pin "P138") (pinfunction "IO_L4P_0_P138") (pintype "bidirectional"))
      (node (ref "U7") (pin "7") (pinfunction "DQ3_7") (pintype "bidirectional"))
    )
    (net (code "48") (name "DQ4") (class "Default")
      (node (ref "U$2") (pin "P134") (pinfunction "IO_L34P_GCLK19_0_P134") (pintype "bidirectional"))
      (node (ref "U7") (pin "8") (pinfunction "DQ4_8") (pintype "bidirectional"))
    )
    (net (code "49") (name "DQ5") (class "Default")
      (node (ref "U$2") (pin "P132") (pinfunction "IO_L35P_GCLK17_0_P132") (pintype "bidirectional"))
      (node (ref "U7") (pin "10") (pinfunction "DQ5_10") (pintype "bidirectional"))
    )
    (net (code "50") (name "DQ6") (class "Default")
      (node (ref "U$2") (pin "P127") (pinfunction "IO_L36P_GCLK15_0_P127") (pintype "bidirectional"))
      (node (ref "U7") (pin "11") (pinfunction "DQ6_11") (pintype "bidirectional"))
    )
    (net (code "51") (name "DQ7") (class "Default")
      (node (ref "U$2") (pin "P124") (pinfunction "IO_L37P_GCLK13_0_P124") (pintype "bidirectional"))
      (node (ref "U7") (pin "13") (pinfunction "DQ7_13") (pintype "bidirectional"))
    )
    (net (code "52") (name "DQ8") (class "Default")
      (node (ref "U$2") (pin "P123") (pinfunction "IO_L37N_GCLK12_0_P123") (pintype "bidirectional"))
      (node (ref "U7") (pin "42") (pinfunction "DQ8_42") (pintype "bidirectional"))
    )
    (net (code "53") (name "DQ9") (class "Default")
      (node (ref "U$2") (pin "P126") (pinfunction "IO_L36N_GCLK14_0_P126") (pintype "bidirectional"))
      (node (ref "U7") (pin "44") (pinfunction "DQ9_44") (pintype "bidirectional"))
    )
    (net (code "54") (name "DQ10") (class "Default")
      (node (ref "U$2") (pin "P131") (pinfunction "IO_L35N_GCLK16_0_P131") (pintype "bidirectional"))
      (node (ref "U7") (pin "45") (pinfunction "DQ10_45") (pintype "bidirectional"))
    )
    (net (code "55") (name "DQ11") (class "Default")
      (node (ref "U$2") (pin "P133") (pinfunction "IO_L34N_GCLK18_0_P133") (pintype "bidirectional"))
      (node (ref "U7") (pin "47") (pinfunction "DQ11_47") (pintype "bidirectional"))
    )
    (net (code "56") (name "DQ12") (class "Default")
      (node (ref "U$2") (pin "P137") (pinfunction "IO_L4N_0_P137") (pintype "bidirectional"))
      (node (ref "U7") (pin "48") (pinfunction "DQ12_48") (pintype "bidirectional"))
    )
    (net (code "57") (name "DQ13") (class "Default")
      (node (ref "U$2") (pin "P139") (pinfunction "IO_L3N_0_P139") (pintype "bidirectional"))
      (node (ref "U7") (pin "50") (pinfunction "DQ13_50") (pintype "bidirectional"))
    )
    (net (code "58") (name "DQ14") (class "Default")
      (node (ref "U$2") (pin "P141") (pinfunction "IO_L2N_0_P141") (pintype "bidirectional"))
      (node (ref "U7") (pin "51") (pinfunction "DQ14_51") (pintype "bidirectional"))
    )
    (net (code "59") (name "DQ15") (class "Default")
      (node (ref "U$2") (pin "P143") (pinfunction "IO_L1N_VREF_0_P143") (pintype "bidirectional"))
      (node (ref "U7") (pin "53") (pinfunction "DQ15_53") (pintype "bidirectional"))
    )
    (net (code "60") (name "DQMH") (class "Default")
      (node (ref "U$2") (pin "P105") (pinfunction "IO_L1P_1_P105") (pintype "bidirectional"))
      (node (ref "U7") (pin "39") (pinfunction "DQMH_39") (pintype "input"))
    )
    (net (code "61") (name "DQML") (class "Default")
      (node (ref "U$2") (pin "P112") (pinfunction "IO_L66P_SCP1_0_P112") (pintype "bidirectional"))
      (node (ref "U7") (pin "15") (pinfunction "DQML_15") (pintype "input"))
    )
    (net (code "62") (name "FLASH_CS") (class "Default")
      (node (ref "R5") (pin "1") (pinfunction "1_1") (pintype "passive"))
      (node (ref "U$2") (pin "P38") (pinfunction "IO_L65N_CSO_B_2_P38") (pintype "bidirectional"))
      (node (ref "U1") (pin "1") (pinfunction "~{CS}_1") (pintype "input"))
    )
    (net (code "63") (name "FLASH_D0") (class "Default")
      (node (ref "U$2") (pin "P64") (pinfunction "IO_L3N_MOSI_CSI_B_MISO0_2_P64") (pintype "bidirectional"))
      (node (ref "U1") (pin "5") (pinfunction "DI(IO0)_5") (pintype "bidirectional"))
    )
    (net (code "64") (name "FLASH_D1") (class "Default")
      (node (ref "U$2") (pin "P65") (pinfunction "IO_L3P_D0_DIN_MISO_MISO1_2_P65") (pintype "bidirectional"))
      (node (ref "U1") (pin "2") (pinfunction "DO(IO1)_2") (pintype "bidirectional"))
    )
    (net (code "65") (name "FLASH_D2") (class "Default")
      (node (ref "R6") (pin "2") (pinfunction "2_2") (pintype "passive"))
      (node (ref "U$2") (pin "P62") (pinfunction "IO_L12P_D1_MISO2_2_P62") (pintype "bidirectional"))
      (node (ref "U1") (pin "3") (pinfunction "~{WP}(IO2)_3") (pintype "bidirectional"))
    )
    (net (code "66") (name "FLASH_D3") (class "Default")
      (node (ref "R7") (pin "2") (pinfunction "2_2") (pintype "passive"))
      (node (ref "U$2") (pin "P61") (pinfunction "IO_L12N_D2_MISO3_2_P61") (pintype "bidirectional"))
      (node (ref "U1") (pin "7") (pinfunction "~{HOLD}(IO3)_7") (pintype "bidirectional"))
    )
    (net (code "67") (name "G1") (class "Default")
      (node (ref "RN3") (pin "3") (pinfunction "1_3") (pintype "passive"))
      (node (ref "U$2") (pin "P11") (pinfunction "IO_L49N_3_P11") (pintype "bidirectional"))
    )
    (net (code "68") (name "G1_GBA") (class "Default")
      (node (ref "RN3") (pin "6") (pinfunction "2_6") (pintype "passive"))
      (node (ref "U5") (pin "24") (pinfunction "24_24") (pintype "passive"))
    )
    (net (code "69") (name "G2") (class "Default")
      (node (ref "RN3") (pin "2") (pinfunction "1_2") (pintype "passive"))
      (node (ref "U$2") (pin "P12") (pinfunction "IO_L49P_3_P12") (pintype "bidirectional"))
    )
    (net (code "70") (name "G2_GBA") (class "Default")
      (node (ref "RN3") (pin "7") (pinfunction "2_7") (pintype "passive"))
      (node (ref "U5") (pin "25") (pinfunction "25_25") (pintype "passive"))
    )
    (net (code "71") (name "G3") (class "Default")
      (node (ref "RN3") (pin "1") (pinfunction "1_1") (pintype "passive"))
      (node (ref "U$2") (pin "P14") (pinfunction "IO_L44N_GCLK20_3_P14") (pintype "bidirectional"))
    )
    (net (code "72") (name "G3_GBA") (class "Default")
      (node (ref "RN3") (pin "8") (pinfunction "2_8") (pintype "passive"))
      (node (ref "U5") (pin "26") (pinfunction "26_26") (pintype "passive"))
    )
    (net (code "73") (name "G4") (class "Default")
      (node (ref "RN4") (pin "4") (pinfunction "1_4") (pintype "passive"))
      (node (ref "U$2") (pin "P26") (pinfunction "IO_L37N_3_P26") (pintype "bidirectional"))
    )
    (net (code "74") (name "G4_GBA") (class "Default")
      (node (ref "RN4") (pin "5") (pinfunction "2_5") (pintype "passive"))
      (node (ref "U5") (pin "27") (pinfunction "27_27") (pintype "passive"))
    )
    (net (code "75") (name "G5") (class "Default")
      (node (ref "RN4") (pin "3") (pinfunction "1_3") (pintype "passive"))
      (node (ref "U$2") (pin "P27") (pinfunction "IO_L37P_3_P27") (pintype "bidirectional"))
    )
    (net (code "76") (name "G5_GBA") (class "Default")
      (node (ref "RN4") (pin "6") (pinfunction "2_6") (pintype "passive"))
      (node (ref "U5") (pin "28") (pinfunction "28_28") (pintype "passive"))
    )
    (net (code "77") (name "GND") (class "Default")
      (node (ref "C1") (pin "2") (pinfunction "2_2") (pintype "passive"))
      (node (ref "C10") (pin "2") (pinfunction "2_2") (pintype "passive"))
      (node (ref "C11") (pin "2") (pinfunction "2_2") (pintype "passive"))
      (node (ref "C12") (pin "2") (pinfunction "2_2") (pintype "passive"))
      (node (ref "C13") (pin "2") (pinfunction "2_2") (pintype "passive"))
      (node (ref "C14") (pin "2") (pinfunction "2_2") (pintype "passive"))
      (node (ref "C15") (pin "2") (pinfunction "2_2") (pintype "passive"))
      (node (ref "C16") (pin "2") (pinfunction "2_2") (pintype "passive"))
      (node (ref "C17") (pin "2") (pinfunction "2_2") (pintype "passive"))
      (node (ref "C18") (pin "2") (pinfunction "2_2") (pintype "passive"))
      (node (ref "C19") (pin "2") (pinfunction "2_2") (pintype "passive"))
      (node (ref "C2") (pin "2") (pinfunction "2_2") (pintype "passive"))
      (node (ref "C20") (pin "2") (pinfunction "2_2") (pintype "passive"))
      (node (ref "C21") (pin "2") (pinfunction "2_2") (pintype "passive"))
      (node (ref "C22") (pin "2") (pinfunction "2_2") (pintype "passive"))
      (node (ref "C23") (pin "2") (pinfunction "2_2") (pintype "passive"))
      (node (ref "C24") (pin "2") (pinfunction "2_2") (pintype "passive"))
      (node (ref "C25") (pin "2") (pinfunction "2_2") (pintype "passive"))
      (node (ref "C26") (pin "2") (pinfunction "-_2") (pintype "bidirectional"))
      (node (ref "C27") (pin "2") (pinfunction "-_2") (pintype "bidirectional"))
      (node (ref "C28") (pin "2") (pinfunction "2_2") (pintype "passive"))
      (node (ref "C3") (pin "2") (pinfunction "2_2") (pintype "passive"))
      (node (ref "C32") (pin "2") (pinfunction "2_2") (pintype "passive"))
      (node (ref "C33") (pin "2") (pinfunction "2_2") (pintype "passive"))
      (node (ref "C34") (pin "2") (pinfunction "2_2") (pintype "passive"))
      (node (ref "C35") (pin "2") (pinfunction "2_2") (pintype "passive"))
      (node (ref "C36") (pin "2") (pinfunction "2_2") (pintype "passive"))
      (node (ref "C37") (pin "2") (pinfunction "2_2") (pintype "passive"))
      (node (ref "C38") (pin "2") (pinfunction "2_2") (pintype "passive"))
      (node (ref "C39") (pin "2") (pinfunction "2_2") (pintype "passive"))
      (node (ref "C4") (pin "2") (pinfunction "2_2") (pintype "passive"))
      (node (ref "C40") (pin "2") (pinfunction "2_2") (pintype "passive"))
      (node (ref "C41") (pin "2") (pinfunction "2_2") (pintype "passive"))
      (node (ref "C5") (pin "2") (pinfunction "2_2") (pintype "passive"))
      (node (ref "C6") (pin "2") (pinfunction "2_2") (pintype "passive"))
      (node (ref "C7") (pin "2") (pinfunction "2_2") (pintype "passive"))
      (node (ref "C8") (pin "2") (pinfunction "2_2") (pintype "passive"))
      (node (ref "C9") (pin "2") (pinfunction "2_2") (pintype "passive"))
      (node (ref "D1") (pin "3") (pinfunction "GND_1_3") (pintype "bidirectional"))
      (node (ref "D1") (pin "8") (pinfunction "GND_2_8") (pintype "bidirectional"))
      (node (ref "D2") (pin "3") (pinfunction "GND_1_3") (pintype "bidirectional"))
      (node (ref "D2") (pin "8") (pinfunction "GND_2_8") (pintype "bidirectional"))
      (node (ref "GND") (pin "TP") (pinfunction "TP_TP") (pintype "input"))
      (node (ref "IC2") (pin "1") (pinfunction "GROUND/ADJUST_1") (pintype "bidirectional"))
      (node (ref "IC3") (pin "1") (pinfunction "GROUND/ADJUST_1") (pintype "bidirectional"))
      (node (ref "IC4") (pin "1") (pinfunction "E0_1") (pintype "bidirectional"))
      (node (ref "IC4") (pin "2") (pinfunction "E1_2") (pintype "bidirectional"))
      (node (ref "IC4") (pin "3") (pinfunction "E2_3") (pintype "bidirectional"))
      (node (ref "IC4") (pin "4") (pinfunction "VSS_4") (pintype "bidirectional"))
      (node (ref "IC4") (pin "7") (pinfunction "~{WC}_7") (pintype "bidirectional"))
      (node (ref "J1") (pin "P$11") (pinfunction "11_P$11") (pintype "bidirectional"))
      (node (ref "J1") (pin "P$2") (pinfunction "2_P$2") (pintype "bidirectional"))
      (node (ref "J1") (pin "P$5") (pinfunction "5_P$5") (pintype "bidirectional"))
      (node (ref "J1") (pin "P$8") (pinfunction "8_P$8") (pintype "bidirectional"))
      (node (ref "LED1") (pin "C") (pinfunction "C_C") (pintype "passive"))
      (node (ref "LED2") (pin "C") (pinfunction "C_C") (pintype "passive"))
      (node (ref "PROG2") (pin "6") (pinfunction "6_6") (pintype "passive"))
      (node (ref "Q1") (pin "1") (pinfunction "S_1") (pintype "passive"))
      (node (ref "R3") (pin "2") (pinfunction "2_2") (pintype "passive"))
      (node (ref "R9") (pin "2") (pinfunction "2_2") (pintype "passive"))
      (node (ref "S1") (pin "1") (pinfunction "GND1_1") (pintype "passive"))
      (node (ref "S1") (pin "4") (pinfunction "GND_4") (pintype "passive"))
      (node (ref "U$1") (pin "2") (pinfunction "GND_2") (pintype "bidirectional"))
      (node (ref "U$2") (pin "P108") (pinfunction "GND_P108") (pintype "bidirectional"))
      (node (ref "U$2") (pin "P113") (pinfunction "GND_P113") (pintype "bidirectional"))
      (node (ref "U$2") (pin "P13") (pinfunction "GND_P13") (pintype "bidirectional"))
      (node (ref "U$2") (pin "P130") (pinfunction "GND_P130") (pintype "bidirectional"))
      (node (ref "U$2") (pin "P136") (pinfunction "GND_P136") (pintype "bidirectional"))
      (node (ref "U$2") (pin "P25") (pinfunction "GND_P25") (pintype "bidirectional"))
      (node (ref "U$2") (pin "P3") (pinfunction "GND_P3") (pintype "bidirectional"))
      (node (ref "U$2") (pin "P49") (pinfunction "GND_P49") (pintype "bidirectional"))
      (node (ref "U$2") (pin "P54") (pinfunction "GND_P54") (pintype "bidirectional"))
      (node (ref "U$2") (pin "P60") (pinfunction "IO_L13P_M1_2_P60") (pintype "bidirectional"))
      (node (ref "U$2") (pin "P68") (pinfunction "GND_P68") (pintype "bidirectional"))
      (node (ref "U$2") (pin "P73") (pinfunction "SUSPEND_P73") (pintype "bidirectional"))
      (node (ref "U$2") (pin "P77") (pinfunction "GND_P77") (pintype "bidirectional"))
      (node (ref "U$2") (pin "P91") (pinfunction "GND_P91") (pintype "bidirectional"))
      (node (ref "U$2") (pin "P96") (pinfunction "GND_P96") (pintype "bidirectional"))
      (node (ref "U$3") (pin "GND") (pinfunction "GND_GND") (pintype "bidirectional"))
      (node (ref "U$5") (pin "GND") (pinfunction "GND_GND") (pintype "bidirectional"))
      (node (ref "U$5") (pin "GND1") (pinfunction "GND_GND1") (pintype "bidirectional"))
      (node (ref "U$5") (pin "P$10") (pinfunction "GND_P$10") (pintype "bidirectional"))
      (node (ref "U$5") (pin "P$7") (pinfunction "GND_P$7") (pintype "bidirectional"))
      (node (ref "U$5") (pin "P$8") (pinfunction "GND_P$8") (pintype "bidirectional"))
      (node (ref "U$5") (pin "P$9") (pinfunction "GND_P$9") (pintype "bidirectional"))
      (node (ref "U1") (pin "4") (pinfunction "GND_4") (pintype "power_in"))
      (node (ref "U2") (pin "10") (pinfunction "GND_10") (pintype "passive"))
      (node (ref "U2") (pin "11") (pinfunction "B8_11") (pintype "bidirectional"))
      (node (ref "U2") (pin "12") (pinfunction "B7_12") (pintype "bidirectional"))
      (node (ref "U2") (pin "13") (pinfunction "B6_13") (pintype "bidirectional"))
      (node (ref "U2") (pin "14") (pinfunction "B5_14") (pintype "bidirectional"))
      (node (ref "U2") (pin "15") (pinfunction "B4_15") (pintype "bidirectional"))
      (node (ref "U2") (pin "16") (pinfunction "B3_16") (pintype "bidirectional"))
      (node (ref "U2") (pin "17") (pinfunction "B2_17") (pintype "bidirectional"))
      (node (ref "U2") (pin "19") (pinfunction "~{OE}_19") (pintype "input"))
      (node (ref "U3") (pin "1") (pinfunction "DIR_1") (pintype "input"))
      (node (ref "U3") (pin "10") (pinfunction "GND_10") (pintype "passive"))
      (node (ref "U3") (pin "11") (pinfunction "B8_11") (pintype "bidirectional"))
      (node (ref "U3") (pin "12") (pinfunction "B7_12") (pintype "bidirectional"))
      (node (ref "U3") (pin "13") (pinfunction "B6_13") (pintype "bidirectional"))
      (node (ref "U3") (pin "14") (pinfunction "B5_14") (pintype "bidirectional"))
      (node (ref "U3") (pin "15") (pinfunction "B4_15") (pintype "bidirectional"))
      (node (ref "U3") (pin "19") (pinfunction "~{OE}_19") (pintype "input"))
      (node (ref "U4") (pin "8") (pinfunction "8_8") (pintype "passive"))
      (node (ref "U5") (pin "35") (pinfunction "35_35") (pintype "passive"))
      (node (ref "U6") (pin "3") (pinfunction "VSS_3") (pintype "power_in"))
      (node (ref "U7") (pin "12") (pinfunction "VSSQ_12") (pintype "power_in"))
      (node (ref "U7") (pin "28") (pinfunction "VSS_28") (pintype "power_in"))
      (node (ref "U7") (pin "41") (pinfunction "VSS_41") (pintype "power_in"))
      (node (ref "U7") (pin "46") (pinfunction "VSSQ_46") (pintype "power_in"))
      (node (ref "U7") (pin "52") (pinfunction "VSSQ_52") (pintype "power_in"))
      (node (ref "U7") (pin "54") (pinfunction "VSS_54") (pintype "power_in"))
      (node (ref "U7") (pin "6") (pinfunction "VSSQ_6") (pintype "power_in"))
      (node (ref "U8") (pin "3") (pinfunction "VSS_3") (pintype "power_in"))
    )
    (net (code "78") (name "LATCH_NES") (class "Default")
      (node (ref "U$3") (pin "LATCH") (pinfunction "LATCH_LATCH") (pintype "bidirectional"))
      (node (ref "U3") (pin "3") (pinfunction "A2_3") (pintype "bidirectional"))
    )
    (net (code "79") (name "LATCH_NES_FPGA") (class "Default")
      (node (ref "U$2") (pin "P22") (pinfunction "IO_L42P_GCLK25_TRDY2_3_P22") (pintype "bidirectional"))
      (node (ref "U3") (pin "17") (pinfunction "B2_17") (pintype "bidirectional"))
    )
    (net (code "80") (name "LEFT_BUTTON") (class "Default")
      (node (ref "U$2") (pin "P48") (pinfunction "IO_L48P_D7_2_P48") (pintype "bidirectional"))
      (node (ref "U4") (pin "3") (pinfunction "3_3") (pintype "passive"))
    )
    (net (code "81") (name "LITKIT") (class "Default")
      (node (ref "R18") (pin "2") (pinfunction "2_2") (pintype "passive"))
      (node (ref "U$2") (pin "P15") (pinfunction "IO_L44P_GCLK21_3_P15") (pintype "bidirectional"))
    )
    (net (code "82") (name "L_BUTTON") (class "Default")
      (node (ref "U$2") (pin "P46") (pinfunction "IO_L49P_D3_2_P46") (pintype "bidirectional"))
      (node (ref "U4") (pin "1") (pinfunction "1_1") (pintype "passive"))
    )
    (net (code "83") (name "MISO{slash}TDO") (class "Default")
      (node (ref "PROG2") (pin "1") (pinfunction "1_1") (pintype "passive"))
      (node (ref "U$2") (pin "P106") (pinfunction "TDO_P106") (pintype "bidirectional"))
    )
    (net (code "84") (name "MOSI{slash}TDI") (class "Default")
      (node (ref "PROG2") (pin "4") (pinfunction "4_4") (pintype "passive"))
      (node (ref "U$2") (pin "P110") (pinfunction "TDI_P110") (pintype "bidirectional"))
    )
    (net (code "85") (name "Net-(C20-Pad1)") (class "Default")
      (node (ref "C20") (pin "1") (pinfunction "1_1") (pintype "passive"))
      (node (ref "R13") (pin "1") (pinfunction "1_1") (pintype "passive"))
      (node (ref "S1") (pin "3") (pinfunction "3_3") (pintype "passive"))
    )
    (net (code "86") (name "Net-(D3-PadC)") (class "Default")
      (node (ref "D3") (pin "C") (pinfunction "C_C") (pintype "passive"))
      (node (ref "U$3") (pin "5V") (pinfunction "5V_5V") (pintype "bidirectional"))
    )
    (net (code "87") (name "Net-(Q1A-G)") (class "Default")
      (node (ref "Q1") (pin "2") (pinfunction "G_2") (pintype "passive"))
      (node (ref "R14") (pin "1") (pinfunction "1_1") (pintype "passive"))
      (node (ref "S1") (pin "2") (pinfunction "2_2") (pintype "passive"))
    )
    (net (code "88") (name "Net-(Q1B-G)") (class "Default")
      (node (ref "Q1") (pin "4") (pinfunction "G_4") (pintype "passive"))
      (node (ref "Q1") (pin "7") (pinfunction "D_7") (pintype "passive"))
      (node (ref "Q1") (pin "8") (pinfunction "D_8") (pintype "passive"))
      (node (ref "R12") (pin "1") (pinfunction "1_1") (pintype "passive"))
      (node (ref "R13") (pin "2") (pinfunction "2_2") (pintype "passive"))
    )
    (net (code "89") (name "Net-(R3-Pad1)") (class "Default")
      (node (ref "R3") (pin "1") (pinfunction "1_1") (pintype "passive"))
      (node (ref "U$5") (pin "CC1") (pinfunction "CC1_CC1") (pintype "bidirectional"))
    )
    (net (code "90") (name "Net-(R9-Pad1)") (class "Default")
      (node (ref "R9") (pin "1") (pinfunction "1_1") (pintype "passive"))
      (node (ref "U$5") (pin "CC2") (pinfunction "CC2_CC2") (pintype "bidirectional"))
    )
    (net (code "91") (name "Net-(U$1-OUT)") (class "Default")
      (node (ref "R8") (pin "1") (pinfunction "1_1") (pintype "passive"))
      (node (ref "U$1") (pin "3") (pinfunction "OUT_3") (pintype "bidirectional"))
    )
    (net (code "92") (name "Net-(U$2-DONE_2)") (class "Default")
      (node (ref "LED1") (pin "A") (pinfunction "A_A") (pintype "passive"))
      (node (ref "R4") (pin "1") (pinfunction "1_1") (pintype "passive"))
      (node (ref "U$2") (pin "P71") (pinfunction "DONE_2_P71") (pintype "bidirectional"))
    )
    (net (code "93") (name "Net-(U$2-IO_L2P_CMPCLK_2)") (class "Default")
      (node (ref "R10") (pin "2") (pinfunction "2_2") (pintype "passive"))
      (node (ref "U$2") (pin "P67") (pinfunction "IO_L2P_CMPCLK_2_P67") (pintype "bidirectional"))
    )
    (net (code "94") (name "Net-(U$2-IO_L65P_INIT_B_2)") (class "Default")
      (node (ref "R1") (pin "2") (pinfunction "2_2") (pintype "passive"))
      (node (ref "U$2") (pin "P39") (pinfunction "IO_L65P_INIT_B_2_P39") (pintype "bidirectional"))
    )
    (net (code "95") (name "Net-(U$2-IO_L74P_AWAKE_1)") (class "Default")
      (node (ref "R11") (pin "2") (pinfunction "2_2") (pintype "passive"))
      (node (ref "U$2") (pin "P75") (pinfunction "IO_L74P_AWAKE_1_P75") (pintype "bidirectional"))
    )
    (net (code "96") (name "Net-(U$2-IO_L83N_VREF_3)") (class "Default")
      (node (ref "LED2") (pin "A") (pinfunction "A_A") (pintype "passive"))
      (node (ref "R15") (pin "2") (pinfunction "2_2") (pintype "passive"))
      (node (ref "U$2") (pin "P1") (pinfunction "IO_L83N_VREF_3_P1") (pintype "bidirectional"))
    )
    (net (code "97") (name "Net-(U$2-PROGRAM_B_2)") (class "Default")
      (node (ref "C24") (pin "1") (pinfunction "1_1") (pintype "passive"))
      (node (ref "R2") (pin "2") (pinfunction "2_2") (pintype "passive"))
      (node (ref "U$2") (pin "P37") (pinfunction "PROGRAM_B_2_P37") (pintype "bidirectional"))
    )
    (net (code "98") (name "Net-(U6-DIN)") (class "Default")
      (node (ref "R18") (pin "1") (pinfunction "1_1") (pintype "passive"))
      (node (ref "U6") (pin "4") (pinfunction "DIN_4") (pintype "input"))
    )
    (net (code "99") (name "Net-(U6-DOUT)") (class "Default")
      (node (ref "U6") (pin "2") (pinfunction "DOUT_2") (pintype "output"))
      (node (ref "U8") (pin "4") (pinfunction "DIN_4") (pintype "input"))
    )
    (net (code "100") (name "Net-(U8-DOUT)") (class "Default")
      (node (ref "LITKIT") (pin "TP") (pinfunction "TP_TP") (pintype "input"))
      (node (ref "U8") (pin "2") (pinfunction "DOUT_2") (pintype "output"))
    )
    (net (code "101") (name "OSC_OUT") (class "Default")
      (node (ref "R8") (pin "2") (pinfunction "2_2") (pintype "passive"))
      (node (ref "U$2") (pin "P55") (pinfunction "IO_L30N_GCLK0_USERCCLK_2_P55") (pintype "bidirectional"))
    )
    (net (code "102") (name "PWR_FET_5V") (class "Default")
      (node (ref "U3") (pin "4") (pinfunction "A3_4") (pintype "bidirectional"))
    )
    (net (code "103") (name "PWR_SW") (class "Default")
      (node (ref "U3") (pin "16") (pinfunction "B3_16") (pintype "bidirectional"))
    )
    (net (code "104") (name "R1") (class "Default")
      (node (ref "RN4") (pin "2") (pinfunction "1_2") (pintype "passive"))
      (node (ref "U$2") (pin "P29") (pinfunction "IO_L36N_3_P29") (pintype "bidirectional"))
    )
    (net (code "105") (name "R1_GBA") (class "Default")
      (node (ref "RN4") (pin "7") (pinfunction "2_7") (pintype "passive"))
      (node (ref "U5") (pin "29") (pinfunction "29_29") (pintype "passive"))
    )
    (net (code "106") (name "R2") (class "Default")
      (node (ref "RN4") (pin "1") (pinfunction "1_1") (pintype "passive"))
      (node (ref "U$2") (pin "P30") (pinfunction "IO_L36P_3_P30") (pintype "bidirectional"))
    )
    (net (code "107") (name "R2_GBA") (class "Default")
      (node (ref "RN4") (pin "8") (pinfunction "2_8") (pintype "passive"))
      (node (ref "U5") (pin "30") (pinfunction "30_30") (pintype "passive"))
    )
    (net (code "108") (name "R3") (class "Default")
      (node (ref "RN5") (pin "4") (pinfunction "1_4") (pintype "passive"))
      (node (ref "U$2") (pin "P32") (pinfunction "IO_L2N_3_P32") (pintype "bidirectional"))
    )
    (net (code "109") (name "R3_GBA") (class "Default")
      (node (ref "RN5") (pin "5") (pinfunction "2_5") (pintype "passive"))
      (node (ref "U5") (pin "31") (pinfunction "31_31") (pintype "passive"))
    )
    (net (code "110") (name "R4") (class "Default")
      (node (ref "RN5") (pin "3") (pinfunction "1_3") (pintype "passive"))
      (node (ref "U$2") (pin "P33") (pinfunction "IO_L2P_3_P33") (pintype "bidirectional"))
    )
    (net (code "111") (name "R4_GBA") (class "Default")
      (node (ref "RN5") (pin "6") (pinfunction "2_6") (pintype "passive"))
      (node (ref "U5") (pin "32") (pinfunction "32_32") (pintype "passive"))
    )
    (net (code "112") (name "R5") (class "Default")
      (node (ref "RN5") (pin "2") (pinfunction "1_2") (pintype "passive"))
      (node (ref "U$2") (pin "P34") (pinfunction "IO_L1N_VREF_3_P34") (pintype "bidirectional"))
    )
    (net (code "113") (name "R5_GBA") (class "Default")
      (node (ref "RN5") (pin "7") (pinfunction "2_7") (pintype "passive"))
      (node (ref "U5") (pin "33") (pinfunction "33_33") (pintype "passive"))
    )
    (net (code "114") (name "RAS") (class "Default")
      (node (ref "U$2") (pin "P101") (pinfunction "IO_L32N_1_P101") (pintype "bidirectional"))
      (node (ref "U7") (pin "18") (pinfunction "~{RAS}_18") (pintype "input"))
    )
    (net (code "115") (name "RIGHT_BUTTON") (class "Default")
      (node (ref "U$2") (pin "P51") (pinfunction "IO_L31P_GCLK31_D14_2_P51") (pintype "bidirectional"))
      (node (ref "U4") (pin "5") (pinfunction "5_5") (pintype "passive"))
    )
    (net (code "116") (name "R_BUTTON") (class "Default")
      (node (ref "U$2") (pin "P58") (pinfunction "IO_L14P_D11_2_P58") (pintype "bidirectional"))
      (node (ref "U4") (pin "10") (pinfunction "10_10") (pintype "passive"))
    )
    (net (code "117") (name "SCK{slash}TCK") (class "Default")
      (node (ref "PROG2") (pin "3") (pinfunction "3_3") (pintype "passive"))
      (node (ref "U$2") (pin "P109") (pinfunction "TCK_P109") (pintype "bidirectional"))
    )
    (net (code "118") (name "SCL") (class "Default")
      (node (ref "IC4") (pin "6") (pinfunction "SCL_6") (pintype "bidirectional"))
      (node (ref "R19") (pin "2") (pinfunction "2_2") (pintype "passive"))
      (node (ref "U$2") (pin "P17") (pinfunction "IO_L43P_GCLK23_3_P17") (pintype "bidirectional"))
    )
    (net (code "119") (name "SCL_HDMI") (class "Default")
      (node (ref "J1") (pin "P$16") (pinfunction "16_P$16") (pintype "bidirectional"))
    )
    (net (code "120") (name "SDA") (class "Default")
      (node (ref "IC4") (pin "5") (pinfunction "SDA_5") (pintype "bidirectional"))
      (node (ref "R17") (pin "2") (pinfunction "2_2") (pintype "passive"))
      (node (ref "U$2") (pin "P16") (pinfunction "IO_L43N_GCLK22_IRDY2_3_P16") (pintype "bidirectional"))
    )
    (net (code "121") (name "SDA_HDMI") (class "Default")
      (node (ref "J1") (pin "P$15") (pinfunction "15_P$15") (pintype "bidirectional"))
    )
    (net (code "122") (name "SELECT_BUTTON") (class "Default")
      (node (ref "U$2") (pin "P56") (pinfunction "IO_L30P_GCLK1_D13_2_P56") (pintype "bidirectional"))
      (node (ref "U4") (pin "6") (pinfunction "6_6") (pintype "passive"))
    )
    (net (code "123") (name "SO1") (class "Default")
      (node (ref "R10") (pin "1") (pinfunction "1_1") (pintype "passive"))
      (node (ref "U4") (pin "13") (pinfunction "13_13") (pintype "passive"))
    )
    (net (code "124") (name "SO2") (class "Default")
      (node (ref "R11") (pin "1") (pinfunction "1_1") (pintype "passive"))
      (node (ref "U4") (pin "14") (pinfunction "14_14") (pintype "passive"))
    )
    (net (code "125") (name "SPL") (class "Default")
      (node (ref "RN1") (pin "6") (pinfunction "2_6") (pintype "passive"))
      (node (ref "U$2") (pin "P2") (pinfunction "IO_L83P_3_P2") (pintype "bidirectional"))
    )
    (net (code "126") (name "SPL_GBA") (class "Default")
      (node (ref "RN1") (pin "3") (pinfunction "1_3") (pintype "passive"))
      (node (ref "U5") (pin "17") (pinfunction "17_17") (pintype "passive"))
    )
    (net (code "127") (name "SPS") (class "Default")
      (node (ref "RN1") (pin "5") (pinfunction "2_5") (pintype "passive"))
      (node (ref "U$2") (pin "P5") (pinfunction "IO_L52N_3_P5") (pintype "bidirectional"))
    )
    (net (code "128") (name "SPS_GBA") (class "Default")
      (node (ref "RN1") (pin "4") (pinfunction "1_4") (pintype "passive"))
      (node (ref "U5") (pin "15") (pinfunction "15_15") (pintype "passive"))
    )
    (net (code "129") (name "SS{slash}TMS") (class "Default")
      (node (ref "PROG2") (pin "5") (pinfunction "5_5") (pintype "passive"))
      (node (ref "U$2") (pin "P107") (pinfunction "TMS_P107") (pintype "bidirectional"))
    )
    (net (code "130") (name "START_BUTTON") (class "Default")
      (node (ref "U$2") (pin "P57") (pinfunction "IO_L14N_D12_2_P57") (pintype "bidirectional"))
      (node (ref "U4") (pin "7") (pinfunction "7_7") (pintype "passive"))
    )
    (net (code "131") (name "TMDSCLK_N") (class "Default")
      (node (ref "D2") (pin "5") (pinfunction "I/O4_5") (pintype "bidirectional"))
      (node (ref "D2") (pin "6") (pinfunction "I/O4_1_6") (pintype "bidirectional"))
      (node (ref "J1") (pin "P$12") (pinfunction "12_P$12") (pintype "bidirectional"))
      (node (ref "U$2") (pin "P114") (pinfunction "IO_L65N_SCP2_0_P114") (pintype "bidirectional"))
    )
    (net (code "132") (name "TMDSCLK_P") (class "Default")
      (node (ref "D2") (pin "4") (pinfunction "I/O3_4") (pintype "bidirectional"))
      (node (ref "D2") (pin "7") (pinfunction "I/O3_1_7") (pintype "bidirectional"))
      (node (ref "J1") (pin "P$10") (pinfunction "10_P$10") (pintype "bidirectional"))
      (node (ref "U$2") (pin "P115") (pinfunction "IO_L65P_SCP3_0_P115") (pintype "bidirectional"))
    )
    (net (code "133") (name "TMDSD0_N") (class "Default")
      (node (ref "D2") (pin "2") (pinfunction "I/O2_2") (pintype "bidirectional"))
      (node (ref "D2") (pin "9") (pinfunction "I/O2_1_9") (pintype "bidirectional"))
      (node (ref "J1") (pin "P$9") (pinfunction "9_P$9") (pintype "bidirectional"))
      (node (ref "U$2") (pin "P116") (pinfunction "IO_L64N_SCP4_0_P116") (pintype "bidirectional"))
    )
    (net (code "134") (name "TMDSD0_P") (class "Default")
      (node (ref "D2") (pin "1") (pinfunction "I/O1_1") (pintype "bidirectional"))
      (node (ref "D2") (pin "10") (pinfunction "I/O1_1_10") (pintype "bidirectional"))
      (node (ref "J1") (pin "P$7") (pinfunction "7_P$7") (pintype "bidirectional"))
      (node (ref "U$2") (pin "P117") (pinfunction "IO_L64P_SCP5_0_P117") (pintype "bidirectional"))
    )
    (net (code "135") (name "TMDSD1_N") (class "Default")
      (node (ref "D1") (pin "5") (pinfunction "I/O4_5") (pintype "bidirectional"))
      (node (ref "D1") (pin "6") (pinfunction "I/O4_1_6") (pintype "bidirectional"))
      (node (ref "J1") (pin "P$6") (pinfunction "6_P$6") (pintype "bidirectional"))
      (node (ref "U$2") (pin "P118") (pinfunction "IO_L63N_SCP6_0_P118") (pintype "bidirectional"))
    )
    (net (code "136") (name "TMDSD1_P") (class "Default")
      (node (ref "D1") (pin "4") (pinfunction "I/O3_4") (pintype "bidirectional"))
      (node (ref "D1") (pin "7") (pinfunction "I/O3_1_7") (pintype "bidirectional"))
      (node (ref "J1") (pin "P$4") (pinfunction "4_P$4") (pintype "bidirectional"))
      (node (ref "U$2") (pin "P119") (pinfunction "IO_L63P_SCP7_0_P119") (pintype "bidirectional"))
    )
    (net (code "137") (name "TMDSD2_N") (class "Default")
      (node (ref "D1") (pin "2") (pinfunction "I/O2_2") (pintype "bidirectional"))
      (node (ref "D1") (pin "9") (pinfunction "I/O2_1_9") (pintype "bidirectional"))
      (node (ref "J1") (pin "P$3") (pinfunction "3_P$3") (pintype "bidirectional"))
      (node (ref "U$2") (pin "P120") (pinfunction "IO_L62N_VREF_0_P120") (pintype "bidirectional"))
    )
    (net (code "138") (name "TMDSD2_P") (class "Default")
      (node (ref "D1") (pin "1") (pinfunction "I/O1_1") (pintype "bidirectional"))
      (node (ref "D1") (pin "10") (pinfunction "I/O1_1_10") (pintype "bidirectional"))
      (node (ref "J1") (pin "P$1") (pinfunction "1_P$1") (pintype "bidirectional"))
      (node (ref "U$2") (pin "P121") (pinfunction "IO_L62P_0_P121") (pintype "bidirectional"))
    )
    (net (code "139") (name "UP_BUTTON") (class "Default")
      (node (ref "U$2") (pin "P47") (pinfunction "IO_L48N_RDWR_B_VREF_2_P47") (pintype "bidirectional"))
      (node (ref "U4") (pin "2") (pinfunction "2_2") (pintype "passive"))
    )
    (net (code "140") (name "WE") (class "Default")
      (node (ref "U$2") (pin "P111") (pinfunction "IO_L66N_SCP0_0_P111") (pintype "bidirectional"))
      (node (ref "U7") (pin "16") (pinfunction "~{WE}_16") (pintype "input"))
    )
    (net (code "141") (name "unconnected-(IC2-VOUT-Pad2)") (class "Default")
      (node (ref "IC2") (pin "2") (pinfunction "VOUT_2") (pintype "bidirectional"))
    )
    (net (code "142") (name "unconnected-(IC3-VOUT-Pad2)") (class "Default")
      (node (ref "IC3") (pin "2") (pinfunction "VOUT_2") (pintype "bidirectional"))
    )
    (net (code "143") (name "unconnected-(J1-13-PadP$13)") (class "Default")
      (node (ref "J1") (pin "P$13") (pinfunction "13_P$13") (pintype "bidirectional"))
    )
    (net (code "144") (name "unconnected-(J1-14-PadP$14)") (class "Default")
      (node (ref "J1") (pin "P$14") (pinfunction "14_P$14") (pintype "bidirectional"))
    )
    (net (code "145") (name "unconnected-(J1-17-PadP$17)") (class "Default")
      (node (ref "J1") (pin "P$17") (pinfunction "17_P$17") (pintype "bidirectional"))
    )
    (net (code "146") (name "unconnected-(J1-19-PadP$19)") (class "Default")
      (node (ref "J1") (pin "P$19") (pinfunction "19_P$19") (pintype "bidirectional"))
    )
    (net (code "147") (name "unconnected-(J1-20-PadP$20)") (class "Default")
      (node (ref "J1") (pin "P$20") (pinfunction "20_P$20") (pintype "bidirectional"))
    )
    (net (code "148") (name "unconnected-(J1-21-PadP$21)") (class "Default")
      (node (ref "J1") (pin "P$21") (pinfunction "21_P$21") (pintype "bidirectional"))
    )
    (net (code "149") (name "unconnected-(J1-22-PadP$22)") (class "Default")
      (node (ref "J1") (pin "P$22") (pinfunction "22_P$22") (pintype "bidirectional"))
    )
    (net (code "150") (name "unconnected-(J1-23-PadP$23)") (class "Default")
      (node (ref "J1") (pin "P$23") (pinfunction "23_P$23") (pintype "bidirectional"))
    )
    (net (code "151") (name "unconnected-(RN1-Pad1)") (class "Default")
      (node (ref "RN1") (pin "1") (pinfunction "1_1") (pintype "passive"))
    )
    (net (code "152") (name "unconnected-(RN1A-2-Pad8)") (class "Default")
      (node (ref "RN1") (pin "8") (pinfunction "2_8") (pintype "passive"))
    )
    (net (code "153") (name "unconnected-(RN1B-1-Pad2)") (class "Default")
      (node (ref "RN1") (pin "2") (pinfunction "1_2") (pintype "passive"))
    )
    (net (code "154") (name "unconnected-(RN1B-2-Pad7)") (class "Default")
      (node (ref "RN1") (pin "7") (pinfunction "2_7") (pintype "passive"))
    )
    (net (code "155") (name "unconnected-(U$2-CMPCS_B_2-PadP72)") (class "Default")
      (node (ref "U$2") (pin "P72") (pinfunction "CMPCS_B_2_P72") (pintype "bidirectional"))
    )
    (net (code "156") (name "unconnected-(U$2-IO_L41P_GCLK27_3-PadP24)") (class "Default")
      (node (ref "U$2") (pin "P24") (pinfunction "IO_L41P_GCLK27_3_P24") (pintype "bidirectional"))
    )
    (net (code "157") (name "unconnected-(U$2-IO_L47N_1-PadP78)") (class "Default")
      (node (ref "U$2") (pin "P78") (pinfunction "IO_L47N_1_P78") (pintype "bidirectional"))
    )
    (net (code "158") (name "unconnected-(U$2-IO_L49N_D4_2-PadP45)") (class "Default")
      (node (ref "U$2") (pin "P45") (pinfunction "IO_L49N_D4_2_P45") (pintype "bidirectional"))
    )
    (net (code "159") (name "unconnected-(U$2-IO_L62N_D6_2-PadP43)") (class "Default")
      (node (ref "U$2") (pin "P43") (pinfunction "IO_L62N_D6_2_P43") (pintype "bidirectional"))
    )
    (net (code "160") (name "unconnected-(U$2-IO_L62P_D5_2-PadP44)") (class "Default")
      (node (ref "U$2") (pin "P44") (pinfunction "IO_L62P_D5_2_P44") (pintype "bidirectional"))
    )
    (net (code "161") (name "unconnected-(U$2-IO_L64N_D9_2-PadP40)") (class "Default")
      (node (ref "U$2") (pin "P40") (pinfunction "IO_L64N_D9_2_P40") (pintype "bidirectional"))
    )
    (net (code "162") (name "unconnected-(U$2-IO_L64P_D8_2-PadP41)") (class "Default")
      (node (ref "U$2") (pin "P41") (pinfunction "IO_L64P_D8_2_P41") (pintype "bidirectional"))
    )
    (net (code "163") (name "unconnected-(U$2-IO_L74N_DOUT_BUSY_1-PadP74)") (class "Default")
      (node (ref "U$2") (pin "P74") (pinfunction "IO_L74N_DOUT_BUSY_1_P74") (pintype "bidirectional"))
    )
    (net (code "164") (name "unconnected-(U$3-NC-PadN{slash}A)") (class "Default")
      (node (ref "U$3") (pin "N/A") (pinfunction "NC_N/A") (pintype "bidirectional"))
    )
    (net (code "165") (name "unconnected-(U$3-NC2-PadN{slash}A2)") (class "Default")
      (node (ref "U$3") (pin "N/A2") (pinfunction "NC2_N/A2") (pintype "bidirectional"))
    )
    (net (code "166") (name "unconnected-(U2-A2-Pad3)") (class "Default")
      (node (ref "U2") (pin "3") (pinfunction "A2_3") (pintype "bidirectional"))
    )
    (net (code "167") (name "unconnected-(U2-A3-Pad4)") (class "Default")
      (node (ref "U2") (pin "4") (pinfunction "A3_4") (pintype "bidirectional"))
    )
    (net (code "168") (name "unconnected-(U2-A4-Pad5)") (class "Default")
      (node (ref "U2") (pin "5") (pinfunction "A4_5") (pintype "bidirectional"))
    )
    (net (code "169") (name "unconnected-(U2-A5-Pad6)") (class "Default")
      (node (ref "U2") (pin "6") (pinfunction "A5_6") (pintype "bidirectional"))
    )
    (net (code "170") (name "unconnected-(U2-A6-Pad7)") (class "Default")
      (node (ref "U2") (pin "7") (pinfunction "A6_7") (pintype "bidirectional"))
    )
    (net (code "171") (name "unconnected-(U2-A7-Pad8)") (class "Default")
      (node (ref "U2") (pin "8") (pinfunction "A7_8") (pintype "bidirectional"))
    )
    (net (code "172") (name "unconnected-(U2-A8-Pad9)") (class "Default")
      (node (ref "U2") (pin "9") (pinfunction "A8_9") (pintype "bidirectional"))
    )
    (net (code "173") (name "unconnected-(U3-A4-Pad5)") (class "Default")
      (node (ref "U3") (pin "5") (pinfunction "A4_5") (pintype "bidirectional"))
    )
    (net (code "174") (name "unconnected-(U3-A5-Pad6)") (class "Default")
      (node (ref "U3") (pin "6") (pinfunction "A5_6") (pintype "bidirectional"))
    )
    (net (code "175") (name "unconnected-(U3-A6-Pad7)") (class "Default")
      (node (ref "U3") (pin "7") (pinfunction "A6_7") (pintype "bidirectional"))
    )
    (net (code "176") (name "unconnected-(U3-A7-Pad8)") (class "Default")
      (node (ref "U3") (pin "8") (pinfunction "A7_8") (pintype "bidirectional"))
    )
    (net (code "177") (name "unconnected-(U3-A8-Pad9)") (class "Default")
      (node (ref "U3") (pin "9") (pinfunction "A8_9") (pintype "bidirectional"))
    )
    (net (code "178") (name "unconnected-(U4-Pad15)") (class "Default")
      (node (ref "U4") (pin "15") (pinfunction "15_15") (pintype "passive"))
    )
    (net (code "179") (name "unconnected-(U4-Pad16)") (class "Default")
      (node (ref "U4") (pin "16") (pinfunction "16_16") (pintype "passive"))
    )
    (net (code "180") (name "unconnected-(U5-Pad1)") (class "Default")
      (node (ref "U5") (pin "1") (pinfunction "1_1") (pintype "passive"))
    )
    (net (code "181") (name "unconnected-(U5-Pad2)") (class "Default")
      (node (ref "U5") (pin "2") (pinfunction "2_2") (pintype "passive"))
    )
    (net (code "182") (name "unconnected-(U5-Pad3)") (class "Default")
      (node (ref "U5") (pin "3") (pinfunction "3_3") (pintype "passive"))
    )
    (net (code "183") (name "unconnected-(U5-Pad4)") (class "Default")
      (node (ref "U5") (pin "4") (pinfunction "4_4") (pintype "passive"))
    )
    (net (code "184") (name "unconnected-(U5-Pad5)") (class "Default")
      (node (ref "U5") (pin "5") (pinfunction "5_5") (pintype "passive"))
    )
    (net (code "185") (name "unconnected-(U5-Pad6)") (class "Default")
      (node (ref "U5") (pin "6") (pinfunction "6_6") (pintype "passive"))
    )
    (net (code "186") (name "unconnected-(U5-Pad7)") (class "Default")
      (node (ref "U5") (pin "7") (pinfunction "7_7") (pintype "passive"))
    )
    (net (code "187") (name "unconnected-(U5-Pad8)") (class "Default")
      (node (ref "U5") (pin "8") (pinfunction "8_8") (pintype "passive"))
    )
    (net (code "188") (name "unconnected-(U5-Pad9)") (class "Default")
      (node (ref "U5") (pin "9") (pinfunction "9_9") (pintype "passive"))
    )
    (net (code "189") (name "unconnected-(U5-Pad10)") (class "Default")
      (node (ref "U5") (pin "10") (pinfunction "10_10") (pintype "passive"))
    )
    (net (code "190") (name "unconnected-(U5-Pad11)") (class "Default")
      (node (ref "U5") (pin "11") (pinfunction "11_11") (pintype "passive"))
    )
    (net (code "191") (name "unconnected-(U5-Pad12)") (class "Default")
      (node (ref "U5") (pin "12") (pinfunction "12_12") (pintype "passive"))
    )
    (net (code "192") (name "unconnected-(U5-Pad13)") (class "Default")
      (node (ref "U5") (pin "13") (pinfunction "13_13") (pintype "passive"))
    )
    (net (code "193") (name "unconnected-(U5-Pad14)") (class "Default")
      (node (ref "U5") (pin "14") (pinfunction "14_14") (pintype "passive"))
    )
    (net (code "194") (name "unconnected-(U5-Pad16)") (class "Default")
      (node (ref "U5") (pin "16") (pinfunction "16_16") (pintype "passive"))
    )
    (net (code "195") (name "unconnected-(U5-Pad23)") (class "Default")
      (node (ref "U5") (pin "23") (pinfunction "23_23") (pintype "passive"))
    )
    (net (code "196") (name "unconnected-(U5-Pad34)") (class "Default")
      (node (ref "U5") (pin "34") (pinfunction "34_34") (pintype "passive"))
    )
    (net (code "197") (name "unconnected-(U5-Pad36)") (class "Default")
      (node (ref "U5") (pin "36") (pinfunction "36_36") (pintype "passive"))
    )
    (net (code "198") (name "unconnected-(U5-Pad37)") (class "Default")
      (node (ref "U5") (pin "37") (pinfunction "37_37") (pintype "passive"))
    )
    (net (code "199") (name "unconnected-(U5-Pad39)") (class "Default")
      (node (ref "U5") (pin "39") (pinfunction "39_39") (pintype "passive"))
    )
    (net (code "200") (name "unconnected-(U5-Pad40)") (class "Default")
      (node (ref "U5") (pin "40") (pinfunction "40_40") (pintype "passive"))
    )
  )
)
